# AutomaticSolarTracker.net
KiCad netlist of a schematic drawn in Altium Designer
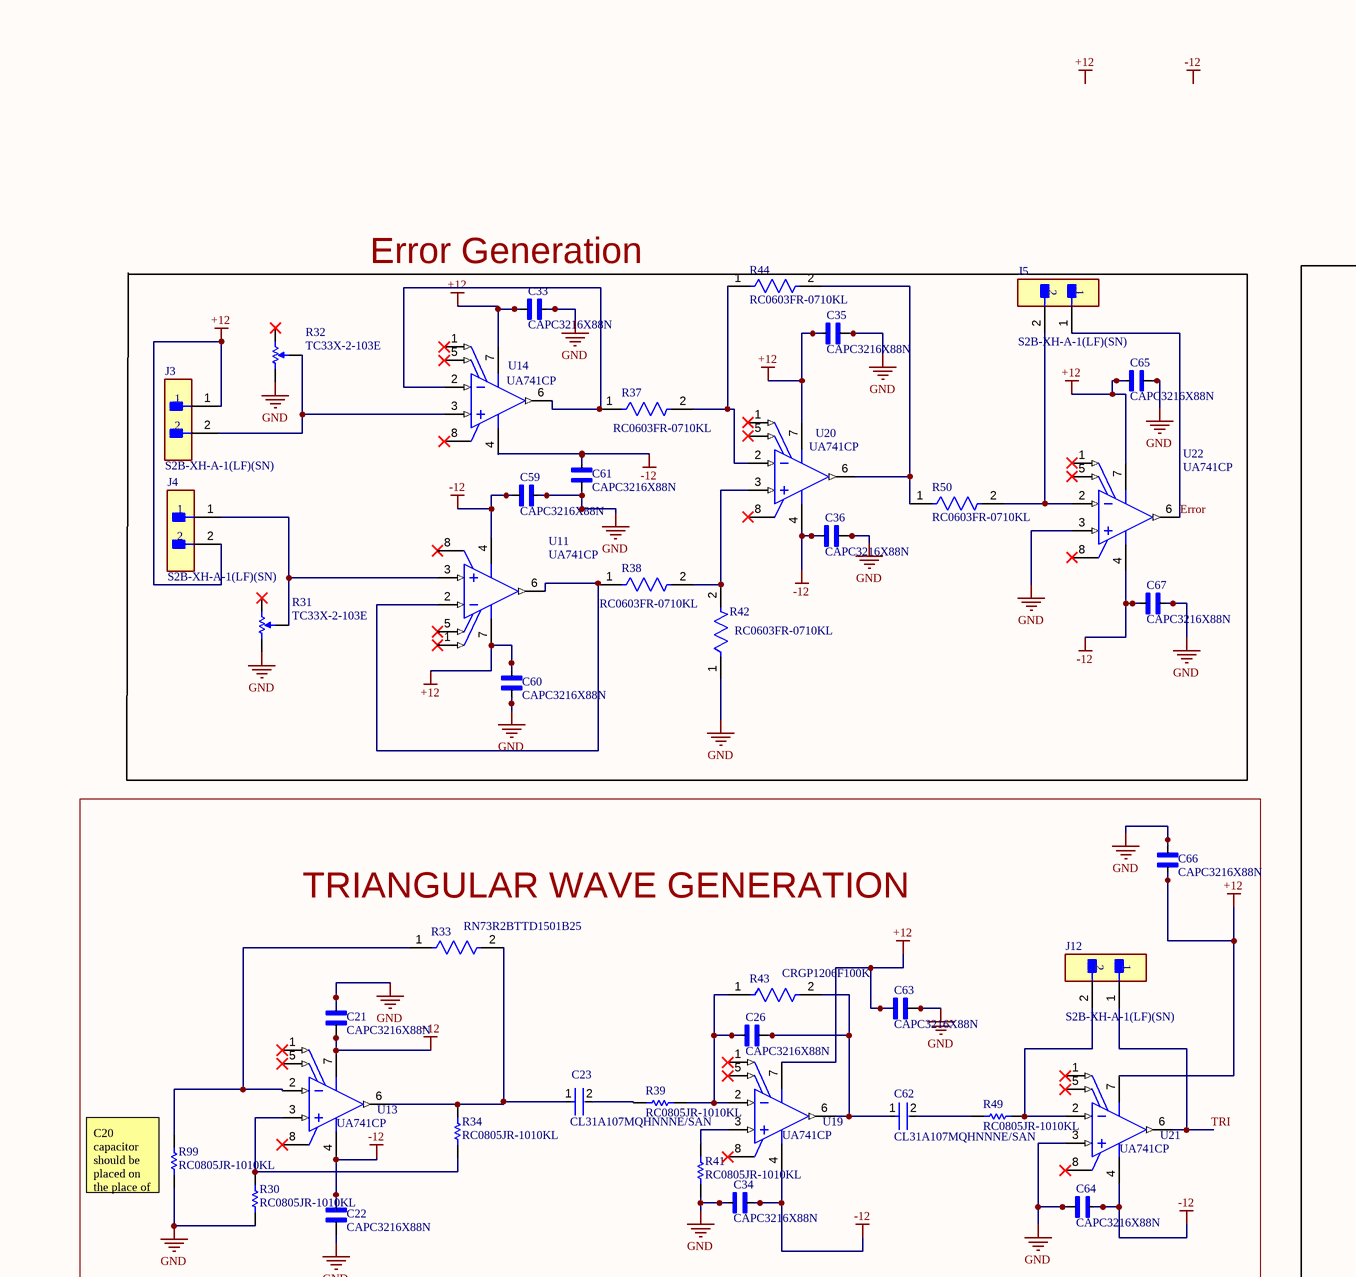
[diagram p0: AutomaticSolarTracker.SchDoc, top left]
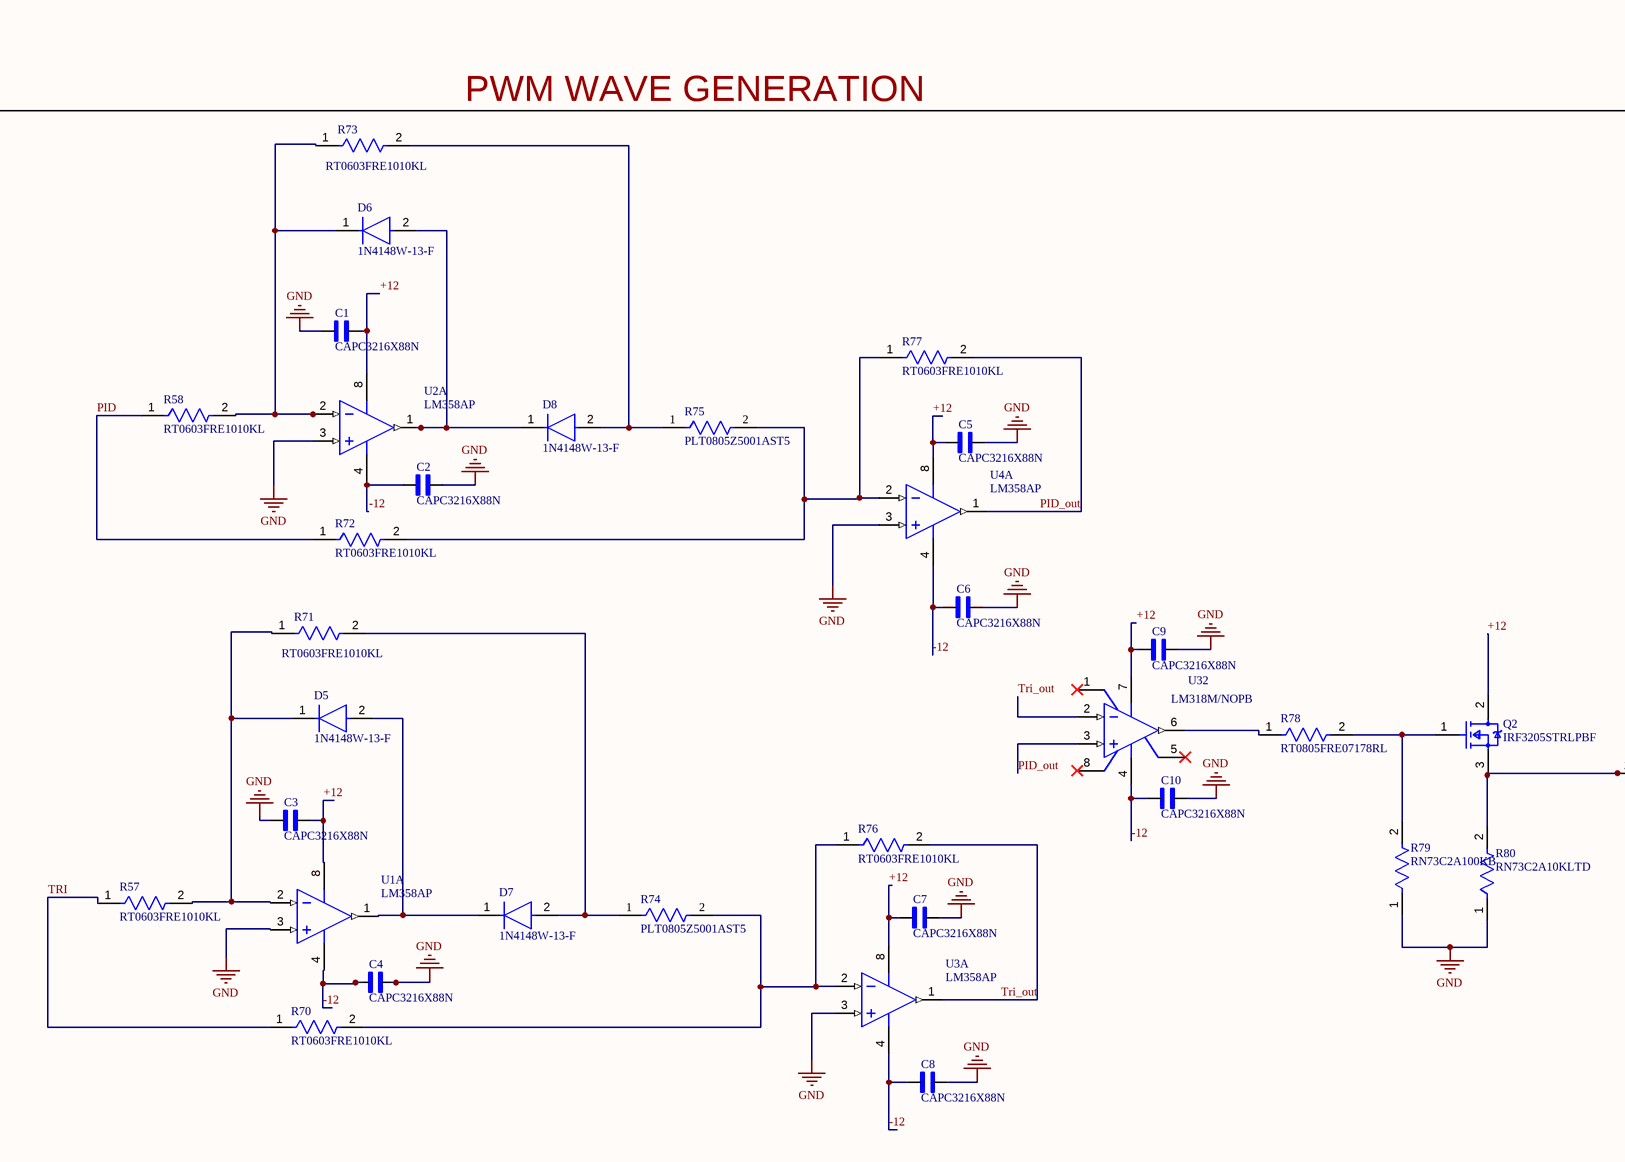
[diagram p1: AutomaticSolarTracker.SchDoc, top middle]
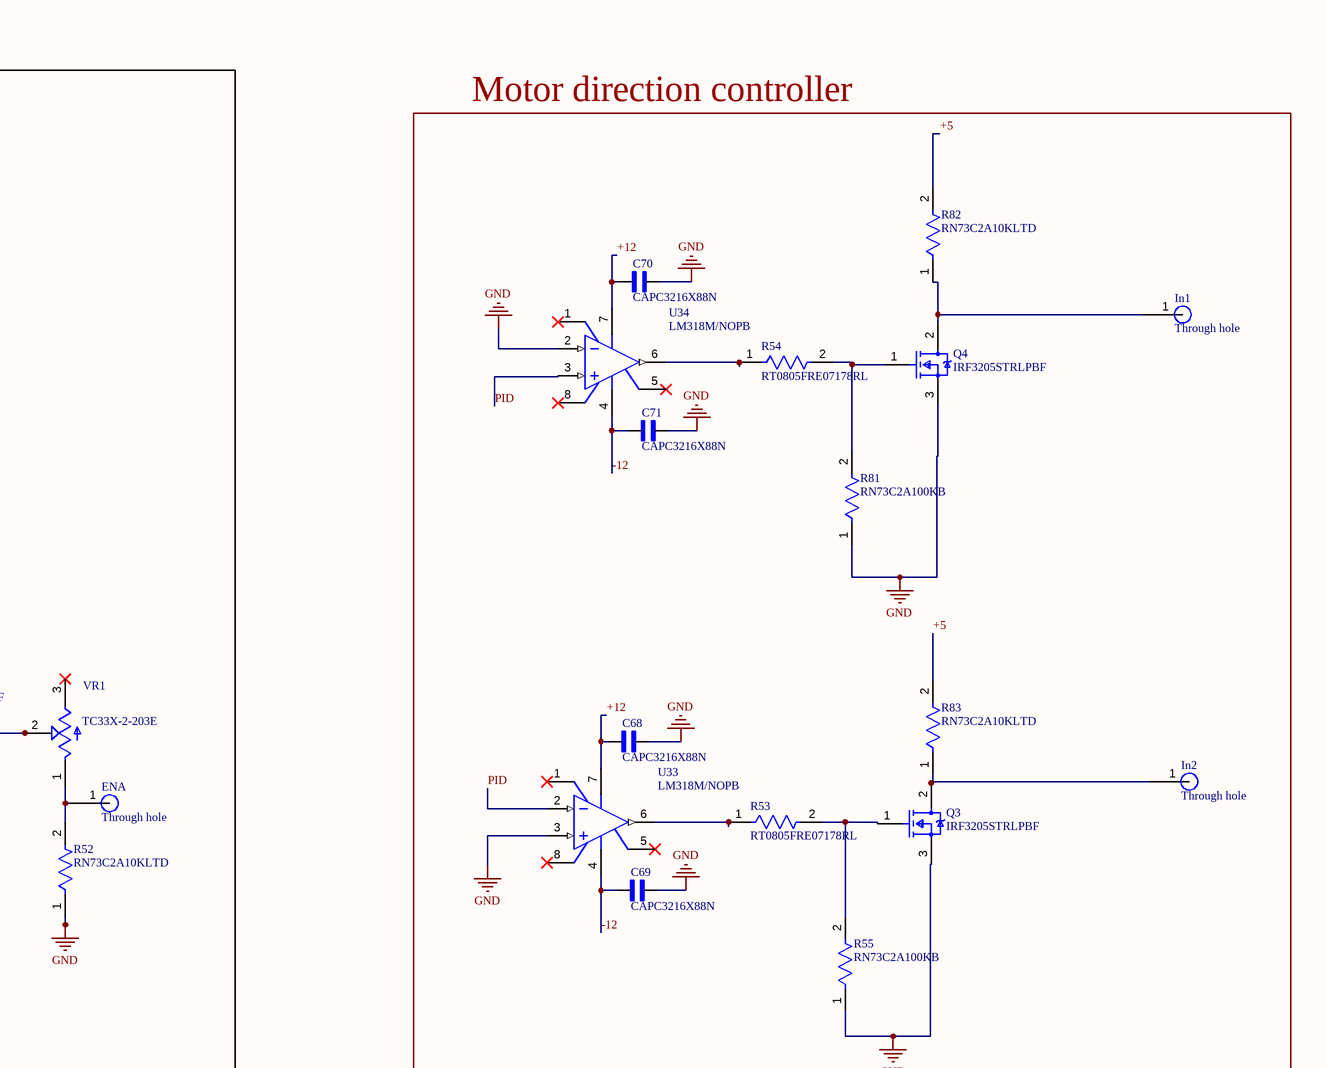
[diagram p2: AutomaticSolarTracker.SchDoc, top right]
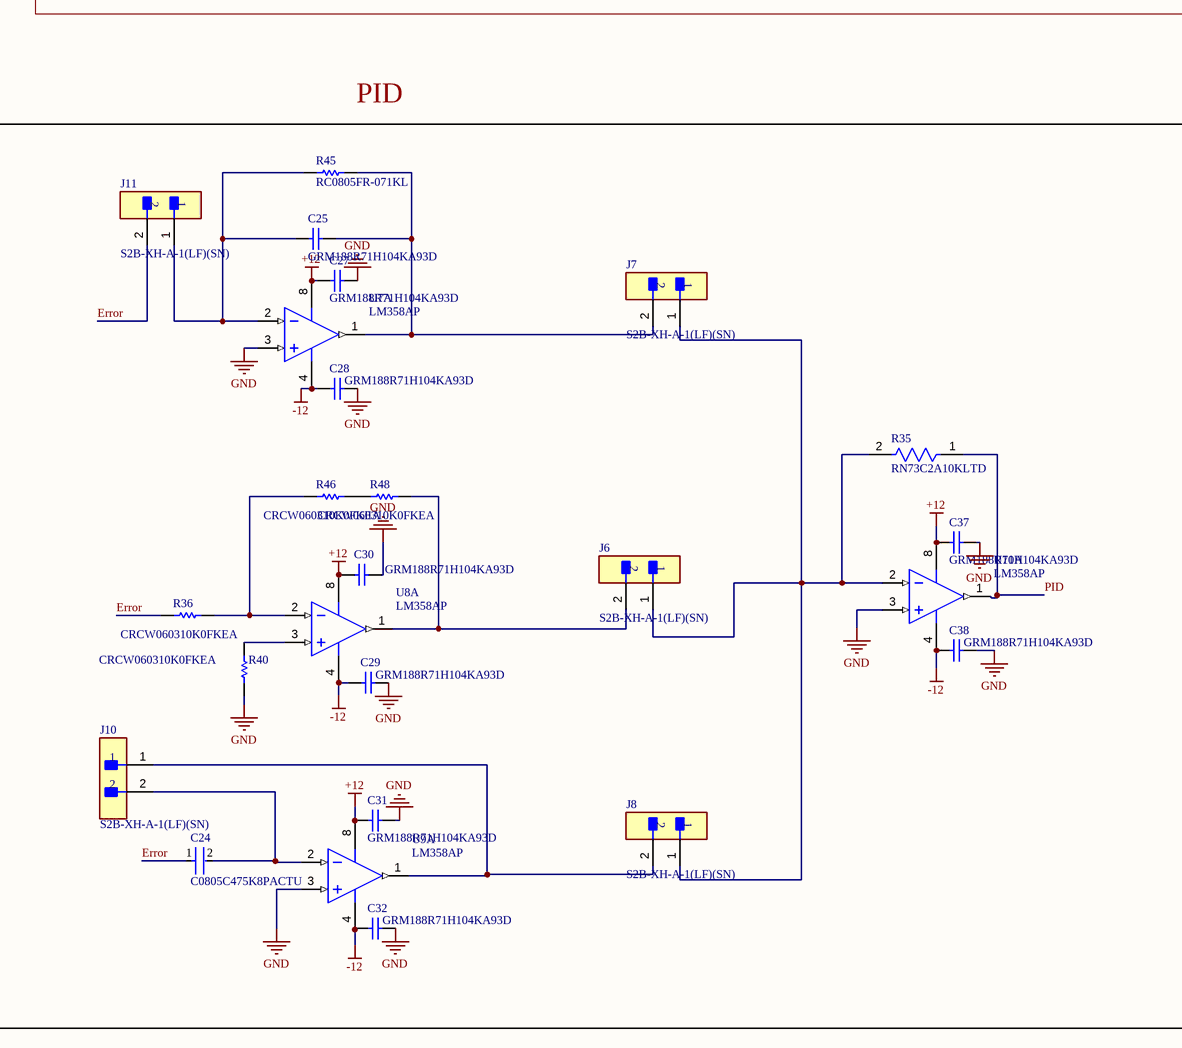
[diagram p3: AutomaticSolarTracker.SchDoc, bottom left]
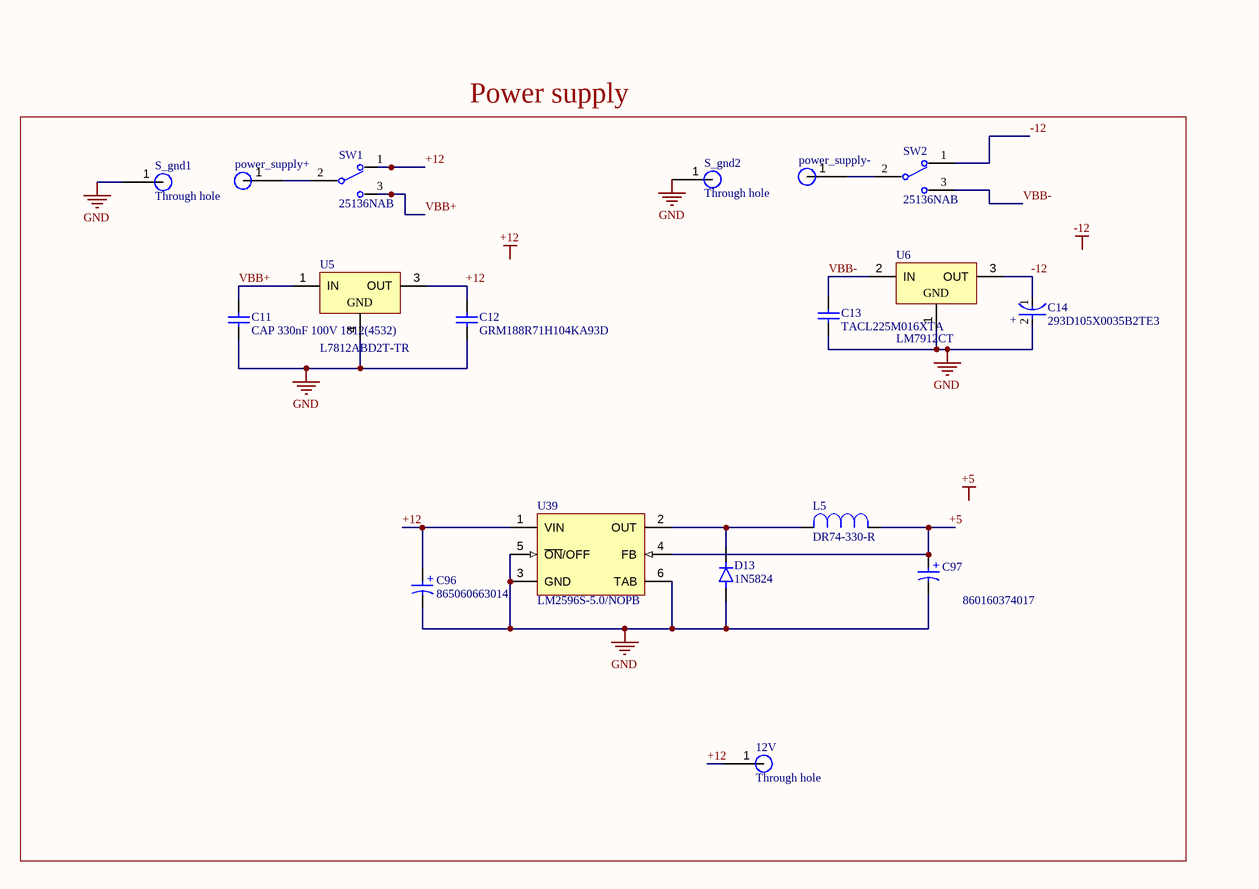
[diagram p4: AutomaticSolarTracker.SchDoc, bottom middle]

(export (version "E")
  (design (tool "Eeschema 10.0.6"))
  (components
    (comp (ref "12V")
      (value "Through hole")
      (footprint "Through hole")
      (libsource (lib "Schlib") (part "Through hole"))
    )
    (comp (ref "C1")
      (value "CAPC3216X88N")
      (footprint "CAPC3216X88N.")
      (description "Multilayer Ceramic Capacitors MLCC - SMD/SMT 50V 0.1uF X7R 1206 10% AEC-Q200")
      (fields
        (field (name "MANUFACTURER") "KEMET")
        (field (name "MANUFACTURER PART NUMBER") "C1206C104K5RACAUTO")
      )
      (libsource (lib "Schlib") (part "CAPC3216X88N"))
    )
    (comp (ref "C2")
      (value "CAPC3216X88N")
      (footprint "CAPC3216X88N.")
      (description "Multilayer Ceramic Capacitors MLCC - SMD/SMT 50V 0.1uF X7R 1206 10% AEC-Q200")
      (fields
        (field (name "MANUFACTURER") "KEMET")
        (field (name "MANUFACTURER PART NUMBER") "C1206C104K5RACAUTO")
      )
      (libsource (lib "Schlib") (part "CAPC3216X88N"))
    )
    (comp (ref "C3")
      (value "CAPC3216X88N")
      (footprint "CAPC3216X88N.")
      (description "Multilayer Ceramic Capacitors MLCC - SMD/SMT 50V 0.1uF X7R 1206 10% AEC-Q200")
      (fields
        (field (name "MANUFACTURER") "KEMET")
        (field (name "MANUFACTURER PART NUMBER") "C1206C104K5RACAUTO")
      )
      (libsource (lib "Schlib") (part "CAPC3216X88N"))
    )
    (comp (ref "C4")
      (value "CAPC3216X88N")
      (footprint "CAPC3216X88N.")
      (description "Multilayer Ceramic Capacitors MLCC - SMD/SMT 50V 0.1uF X7R 1206 10% AEC-Q200")
      (fields
        (field (name "MANUFACTURER") "KEMET")
        (field (name "MANUFACTURER PART NUMBER") "C1206C104K5RACAUTO")
      )
      (libsource (lib "Schlib") (part "CAPC3216X88N"))
    )
    (comp (ref "C5")
      (value "CAPC3216X88N")
      (footprint "CAPC3216X88N.")
      (description "Multilayer Ceramic Capacitors MLCC - SMD/SMT 50V 0.1uF X7R 1206 10% AEC-Q200")
      (fields
        (field (name "MANUFACTURER") "KEMET")
        (field (name "MANUFACTURER PART NUMBER") "C1206C104K5RACAUTO")
      )
      (libsource (lib "Schlib") (part "CAPC3216X88N"))
    )
    (comp (ref "C6")
      (value "CAPC3216X88N")
      (footprint "CAPC3216X88N.")
      (description "Multilayer Ceramic Capacitors MLCC - SMD/SMT 50V 0.1uF X7R 1206 10% AEC-Q200")
      (fields
        (field (name "MANUFACTURER") "KEMET")
        (field (name "MANUFACTURER PART NUMBER") "C1206C104K5RACAUTO")
      )
      (libsource (lib "Schlib") (part "CAPC3216X88N"))
    )
    (comp (ref "C7")
      (value "CAPC3216X88N")
      (footprint "CAPC3216X88N.")
      (description "Multilayer Ceramic Capacitors MLCC - SMD/SMT 50V 0.1uF X7R 1206 10% AEC-Q200")
      (fields
        (field (name "MANUFACTURER") "KEMET")
        (field (name "MANUFACTURER PART NUMBER") "C1206C104K5RACAUTO")
      )
      (libsource (lib "Schlib") (part "CAPC3216X88N"))
    )
    (comp (ref "C8")
      (value "CAPC3216X88N")
      (footprint "CAPC3216X88N.")
      (description "Multilayer Ceramic Capacitors MLCC - SMD/SMT 50V 0.1uF X7R 1206 10% AEC-Q200")
      (fields
        (field (name "MANUFACTURER") "KEMET")
        (field (name "MANUFACTURER PART NUMBER") "C1206C104K5RACAUTO")
      )
      (libsource (lib "Schlib") (part "CAPC3216X88N"))
    )
    (comp (ref "C9")
      (value "CAPC3216X88N")
      (footprint "CAPC3216X88N.")
      (description "Multilayer Ceramic Capacitors MLCC - SMD/SMT 50V 0.1uF X7R 1206 10% AEC-Q200")
      (fields
        (field (name "MANUFACTURER") "KEMET")
        (field (name "MANUFACTURER PART NUMBER") "C1206C104K5RACAUTO")
      )
      (libsource (lib "Schlib") (part "CAPC3216X88N"))
    )
    (comp (ref "C10")
      (value "CAPC3216X88N")
      (footprint "CAPC3216X88N.")
      (description "Multilayer Ceramic Capacitors MLCC - SMD/SMT 50V 0.1uF X7R 1206 10% AEC-Q200")
      (fields
        (field (name "MANUFACTURER") "KEMET")
        (field (name "MANUFACTURER PART NUMBER") "C1206C104K5RACAUTO")
      )
      (libsource (lib "Schlib") (part "CAPC3216X88N"))
    )
    (comp (ref "C11")
      (value "CAP 330nF 100V 1812(4532)")
      (footprint "CAPC1812(4532)125_L")
      (description "CAP 330nF 100V ±20% 1812 (4532 Metric) Thickness 1.25mm SMD")
      (fields (field (name "TOLERANCE") "Â±20%"))
      (libsource (lib "Altium Content Vault") (part "CAP"))
    )
    (comp (ref "C12")
      (value "GRM188R71H104KA93D")
      (footprint "CAPC1608X90X35ML10T15")
      (description "Chip Capacitor, 0.1 uF, +/- 10%, 50 V, -55 to 125 degC, 0603 (1608 Metric), RoHS, Tape and Reel")
      (fields (field (name "TOLERANCE") "10%") (field (name "VOLTAGE") "50V"))
      (libsource (lib "Altium Content Vault") (part "CAP-NP-2"))
    )
    (comp (ref "C13")
      (value "TACL225M016XTA")
      (footprint "CAPC1609X100X15ML20")
      (fields (field (name "MANUFACTURER") "AVX Interconnect / Elco"))
      (libsource (lib "Altium Content Vault") (part "CAP"))
    )
    (comp (ref "C14")
      (value "293D105X0035B2TE3")
      (footprint "FP-293DB-MFG")
      (fields (field (name "TOLERANCE") "20%"))
      (libsource (lib "Altium Content Vault") (part "a00bbbee19879c290e62620ae7e47b1"))
    )
    (comp (ref "C21")
      (value "CAPC3216X88N")
      (footprint "CAPC3216X88N.")
      (description "Multilayer Ceramic Capacitors MLCC - SMD/SMT 50V 0.1uF X7R 1206 10% AEC-Q200")
      (fields
        (field (name "MANUFACTURER") "KEMET")
        (field (name "MANUFACTURER PART NUMBER") "C1206C104K5RACAUTO")
      )
      (libsource (lib "") (part "CAPC3216X88N_1"))
    )
    (comp (ref "C22")
      (value "CAPC3216X88N")
      (footprint "CAPC3216X88N.")
      (description "Multilayer Ceramic Capacitors MLCC - SMD/SMT 50V 0.1uF X7R 1206 10% AEC-Q200")
      (fields
        (field (name "MANUFACTURER") "KEMET")
        (field (name "MANUFACTURER PART NUMBER") "C1206C104K5RACAUTO")
      )
      (libsource (lib "") (part "CAPC3216X88N_1"))
    )
    (comp (ref "C23")
      (value "CL31A107MQHNNNE/SAN")
      (footprint "FP-CL31-IPC_C")
      (description "Cap Ceramic 100uF 6.3V X5R ±20% SMD 1206 +85°C Embossed T/R")
      (libsource (lib "Altium Content Vault") (part "b4654b650e69147ec39a6b967a45e02"))
    )
    (comp (ref "C24")
      (value "C0805C475K8PACTU")
      (footprint "FP-C0805C475K8PACTU-MFG")
      (description "CAP CER 4.7UF 10V X5R 0805")
      (fields (field (name "TOLERANCE") "10%") (field (name "VOLTAGE") "10V"))
      (libsource (lib "Altium Content Vault") (part "e9c51b7dd13d4faca003ae77663ab08"))
    )
    (comp (ref "C25")
      (value "GRM188R71H104KA93D")
      (footprint "CAPC1608X90X35ML10T15")
      (description "Chip Capacitor, 0.1 uF, +/- 10%, 50 V, -55 to 125 degC, 0603 (1608 Metric), RoHS, Tape and Reel")
      (fields (field (name "TOLERANCE") "10%") (field (name "VOLTAGE") "50V"))
      (libsource (lib "Altium Content Vault") (part "CAP-NP-2"))
    )
    (comp (ref "C26")
      (value "CAPC3216X88N")
      (footprint "CAPC3216X88N.")
      (description "Multilayer Ceramic Capacitors MLCC - SMD/SMT 50V 0.1uF X7R 1206 10% AEC-Q200")
      (fields
        (field (name "MANUFACTURER") "KEMET")
        (field (name "MANUFACTURER PART NUMBER") "C1206C104K5RACAUTO")
      )
      (libsource (lib "Schlib") (part "CAPC3216X88N"))
    )
    (comp (ref "C27")
      (value "GRM188R71H104KA93D")
      (footprint "CAPC1608X90X35ML10T15")
      (description "Chip Capacitor, 0.1 uF, +/- 10%, 50 V, -55 to 125 degC, 0603 (1608 Metric), RoHS, Tape and Reel")
      (fields (field (name "TOLERANCE") "10%") (field (name "VOLTAGE") "50V"))
      (libsource (lib "Altium Content Vault") (part "CAP-NP-2"))
    )
    (comp (ref "C28")
      (value "GRM188R71H104KA93D")
      (footprint "CAPC1608X90X35ML10T15")
      (description "Chip Capacitor, 0.1 uF, +/- 10%, 50 V, -55 to 125 degC, 0603 (1608 Metric), RoHS, Tape and Reel")
      (fields (field (name "TOLERANCE") "10%") (field (name "VOLTAGE") "50V"))
      (libsource (lib "Altium Content Vault") (part "CAP-NP-2"))
    )
    (comp (ref "C29")
      (value "GRM188R71H104KA93D")
      (footprint "CAPC1608X90X35ML10T15")
      (description "Chip Capacitor, 0.1 uF, +/- 10%, 50 V, -55 to 125 degC, 0603 (1608 Metric), RoHS, Tape and Reel")
      (fields (field (name "TOLERANCE") "10%") (field (name "VOLTAGE") "50V"))
      (libsource (lib "Altium Content Vault") (part "CAP-NP-2"))
    )
    (comp (ref "C30")
      (value "GRM188R71H104KA93D")
      (footprint "CAPC1608X90X35ML10T15")
      (description "Chip Capacitor, 0.1 uF, +/- 10%, 50 V, -55 to 125 degC, 0603 (1608 Metric), RoHS, Tape and Reel")
      (fields (field (name "TOLERANCE") "10%") (field (name "VOLTAGE") "50V"))
      (libsource (lib "Altium Content Vault") (part "CAP-NP-2"))
    )
    (comp (ref "C31")
      (value "GRM188R71H104KA93D")
      (footprint "CAPC1608X90X35ML10T15")
      (description "Chip Capacitor, 0.1 uF, +/- 10%, 50 V, -55 to 125 degC, 0603 (1608 Metric), RoHS, Tape and Reel")
      (fields (field (name "TOLERANCE") "10%") (field (name "VOLTAGE") "50V"))
      (libsource (lib "Altium Content Vault") (part "CAP-NP-2"))
    )
    (comp (ref "C32")
      (value "GRM188R71H104KA93D")
      (footprint "CAPC1608X90X35ML10T15")
      (description "Chip Capacitor, 0.1 uF, +/- 10%, 50 V, -55 to 125 degC, 0603 (1608 Metric), RoHS, Tape and Reel")
      (fields (field (name "TOLERANCE") "10%") (field (name "VOLTAGE") "50V"))
      (libsource (lib "Altium Content Vault") (part "CAP-NP-2"))
    )
    (comp (ref "C33")
      (value "CAPC3216X88N")
      (footprint "CAPC3216X88N.")
      (description "Multilayer Ceramic Capacitors MLCC - SMD/SMT 50V 0.1uF X7R 1206 10% AEC-Q200")
      (fields
        (field (name "MANUFACTURER") "KEMET")
        (field (name "MANUFACTURER PART NUMBER") "C1206C104K5RACAUTO")
      )
      (libsource (lib "Schlib") (part "CAPC3216X88N"))
    )
    (comp (ref "C34")
      (value "CAPC3216X88N")
      (footprint "CAPC3216X88N.")
      (description "Multilayer Ceramic Capacitors MLCC - SMD/SMT 50V 0.1uF X7R 1206 10% AEC-Q200")
      (fields
        (field (name "MANUFACTURER") "KEMET")
        (field (name "MANUFACTURER PART NUMBER") "C1206C104K5RACAUTO")
      )
      (libsource (lib "Schlib") (part "CAPC3216X88N"))
    )
    (comp (ref "C35")
      (value "CAPC3216X88N")
      (footprint "CAPC3216X88N.")
      (description "Multilayer Ceramic Capacitors MLCC - SMD/SMT 50V 0.1uF X7R 1206 10% AEC-Q200")
      (fields
        (field (name "MANUFACTURER") "KEMET")
        (field (name "MANUFACTURER PART NUMBER") "C1206C104K5RACAUTO")
      )
      (libsource (lib "Schlib") (part "CAPC3216X88N"))
    )
    (comp (ref "C36")
      (value "CAPC3216X88N")
      (footprint "CAPC3216X88N.")
      (description "Multilayer Ceramic Capacitors MLCC - SMD/SMT 50V 0.1uF X7R 1206 10% AEC-Q200")
      (fields
        (field (name "MANUFACTURER") "KEMET")
        (field (name "MANUFACTURER PART NUMBER") "C1206C104K5RACAUTO")
      )
      (libsource (lib "Schlib") (part "CAPC3216X88N"))
    )
    (comp (ref "C37")
      (value "GRM188R71H104KA93D")
      (footprint "CAPC1608X90X35ML10T15")
      (description "Chip Capacitor, 0.1 uF, +/- 10%, 50 V, -55 to 125 degC, 0603 (1608 Metric), RoHS, Tape and Reel")
      (fields (field (name "TOLERANCE") "10%") (field (name "VOLTAGE") "50V"))
      (libsource (lib "Altium Content Vault") (part "CAP-NP-2"))
    )
    (comp (ref "C38")
      (value "GRM188R71H104KA93D")
      (footprint "CAPC1608X90X35ML10T15")
      (description "Chip Capacitor, 0.1 uF, +/- 10%, 50 V, -55 to 125 degC, 0603 (1608 Metric), RoHS, Tape and Reel")
      (fields (field (name "TOLERANCE") "10%") (field (name "VOLTAGE") "50V"))
      (libsource (lib "Altium Content Vault") (part "CAP-NP-2"))
    )
    (comp (ref "C59")
      (value "CAPC3216X88N")
      (footprint "CAPC3216X88N.")
      (description "Multilayer Ceramic Capacitors MLCC - SMD/SMT 50V 0.1uF X7R 1206 10% AEC-Q200")
      (fields
        (field (name "MANUFACTURER") "KEMET")
        (field (name "MANUFACTURER PART NUMBER") "C1206C104K5RACAUTO")
      )
      (libsource (lib "Schlib") (part "CAPC3216X88N"))
    )
    (comp (ref "C60")
      (value "CAPC3216X88N")
      (footprint "CAPC3216X88N.")
      (description "Multilayer Ceramic Capacitors MLCC - SMD/SMT 50V 0.1uF X7R 1206 10% AEC-Q200")
      (fields
        (field (name "MANUFACTURER") "KEMET")
        (field (name "MANUFACTURER PART NUMBER") "C1206C104K5RACAUTO")
      )
      (libsource (lib "") (part "CAPC3216X88N_1"))
    )
    (comp (ref "C61")
      (value "CAPC3216X88N")
      (footprint "CAPC3216X88N.")
      (description "Multilayer Ceramic Capacitors MLCC - SMD/SMT 50V 0.1uF X7R 1206 10% AEC-Q200")
      (fields
        (field (name "MANUFACTURER") "KEMET")
        (field (name "MANUFACTURER PART NUMBER") "C1206C104K5RACAUTO")
      )
      (libsource (lib "") (part "CAPC3216X88N_1"))
    )
    (comp (ref "C62")
      (value "CL31A107MQHNNNE/SAN")
      (footprint "FP-CL31-IPC_C")
      (description "Cap Ceramic 100uF 6.3V X5R ±20% SMD 1206 +85°C Embossed T/R")
      (libsource (lib "Altium Content Vault") (part "b4654b650e69147ec39a6b967a45e02"))
    )
    (comp (ref "C63")
      (value "CAPC3216X88N")
      (footprint "CAPC3216X88N.")
      (description "Multilayer Ceramic Capacitors MLCC - SMD/SMT 50V 0.1uF X7R 1206 10% AEC-Q200")
      (fields
        (field (name "MANUFACTURER") "KEMET")
        (field (name "MANUFACTURER PART NUMBER") "C1206C104K5RACAUTO")
      )
      (libsource (lib "Schlib") (part "CAPC3216X88N"))
    )
    (comp (ref "C64")
      (value "CAPC3216X88N")
      (footprint "CAPC3216X88N.")
      (description "Multilayer Ceramic Capacitors MLCC - SMD/SMT 50V 0.1uF X7R 1206 10% AEC-Q200")
      (fields
        (field (name "MANUFACTURER") "KEMET")
        (field (name "MANUFACTURER PART NUMBER") "C1206C104K5RACAUTO")
      )
      (libsource (lib "Schlib") (part "CAPC3216X88N"))
    )
    (comp (ref "C65")
      (value "CAPC3216X88N")
      (footprint "CAPC3216X88N.")
      (description "Multilayer Ceramic Capacitors MLCC - SMD/SMT 50V 0.1uF X7R 1206 10% AEC-Q200")
      (fields
        (field (name "MANUFACTURER") "KEMET")
        (field (name "MANUFACTURER PART NUMBER") "C1206C104K5RACAUTO")
      )
      (libsource (lib "Schlib") (part "CAPC3216X88N"))
    )
    (comp (ref "C66")
      (value "CAPC3216X88N")
      (footprint "CAPC3216X88N.")
      (description "Multilayer Ceramic Capacitors MLCC - SMD/SMT 50V 0.1uF X7R 1206 10% AEC-Q200")
      (fields
        (field (name "MANUFACTURER") "KEMET")
        (field (name "MANUFACTURER PART NUMBER") "C1206C104K5RACAUTO")
      )
      (libsource (lib "") (part "CAPC3216X88N_1"))
    )
    (comp (ref "C67")
      (value "CAPC3216X88N")
      (footprint "CAPC3216X88N.")
      (description "Multilayer Ceramic Capacitors MLCC - SMD/SMT 50V 0.1uF X7R 1206 10% AEC-Q200")
      (fields
        (field (name "MANUFACTURER") "KEMET")
        (field (name "MANUFACTURER PART NUMBER") "C1206C104K5RACAUTO")
      )
      (libsource (lib "Schlib") (part "CAPC3216X88N"))
    )
    (comp (ref "C68")
      (value "CAPC3216X88N")
      (footprint "CAPC3216X88N.")
      (description "Multilayer Ceramic Capacitors MLCC - SMD/SMT 50V 0.1uF X7R 1206 10% AEC-Q200")
      (fields
        (field (name "MANUFACTURER") "KEMET")
        (field (name "MANUFACTURER PART NUMBER") "C1206C104K5RACAUTO")
      )
      (libsource (lib "Schlib") (part "CAPC3216X88N"))
    )
    (comp (ref "C69")
      (value "CAPC3216X88N")
      (footprint "CAPC3216X88N.")
      (description "Multilayer Ceramic Capacitors MLCC - SMD/SMT 50V 0.1uF X7R 1206 10% AEC-Q200")
      (fields
        (field (name "MANUFACTURER") "KEMET")
        (field (name "MANUFACTURER PART NUMBER") "C1206C104K5RACAUTO")
      )
      (libsource (lib "Schlib") (part "CAPC3216X88N"))
    )
    (comp (ref "C70")
      (value "CAPC3216X88N")
      (footprint "CAPC3216X88N.")
      (description "Multilayer Ceramic Capacitors MLCC - SMD/SMT 50V 0.1uF X7R 1206 10% AEC-Q200")
      (fields
        (field (name "MANUFACTURER") "KEMET")
        (field (name "MANUFACTURER PART NUMBER") "C1206C104K5RACAUTO")
      )
      (libsource (lib "Schlib") (part "CAPC3216X88N"))
    )
    (comp (ref "C71")
      (value "CAPC3216X88N")
      (footprint "CAPC3216X88N.")
      (description "Multilayer Ceramic Capacitors MLCC - SMD/SMT 50V 0.1uF X7R 1206 10% AEC-Q200")
      (fields
        (field (name "MANUFACTURER") "KEMET")
        (field (name "MANUFACTURER PART NUMBER") "C1206C104K5RACAUTO")
      )
      (libsource (lib "Schlib") (part "CAPC3216X88N"))
    )
    (comp (ref "C96")
      (value "865060663014")
      (footprint "WCAP-ASLL_D16H17")
      (description "865060663014 WCAP-ASLL Aluminum Electrolytic Capacitors")
      (fields (field (name "TOLERANCE") "20%"))
      (libsource (lib "Altium Content Vault") (part "Capacitor_Polarized"))
    )
    (comp (ref "C97")
      (value "860160374017")
      (footprint "WCAP-ATLL_D8H11.5")
      (description "860160374017 Aluminium Electrolytic Capacitor-Leaded Rohs Compliant: Yes")
      (libsource (lib "Altium Content Vault") (part "Capacitor_Polarized"))
    )
    (comp (ref "D5")
      (value "1N4148W-13-F")
      (footprint "FP-SOD123-MFG")
      (description "DIODE GEN PURP 100V 150MA SOD123")
      (fields
        (field (name "OCTOPART") "https://octopart.com/1n4148w-13-f-diodes+inc.-2359612")
        (field (name "MANUFACTURER") "Diodes Inc.")
      )
      (libsource (lib "Altium Content Vault") (part "d7152d700b627762746794eb795d46e"))
    )
    (comp (ref "D6")
      (value "1N4148W-13-F")
      (footprint "FP-SOD123-MFG")
      (description "DIODE GEN PURP 100V 150MA SOD123")
      (fields
        (field (name "OCTOPART") "https://octopart.com/1n4148w-13-f-diodes+inc.-2359612")
        (field (name "MANUFACTURER") "Diodes Inc.")
      )
      (libsource (lib "Altium Content Vault") (part "d7152d700b627762746794eb795d46e"))
    )
    (comp (ref "D7")
      (value "1N4148W-13-F")
      (footprint "FP-SOD123-MFG")
      (description "DIODE GEN PURP 100V 150MA SOD123")
      (fields
        (field (name "OCTOPART") "https://octopart.com/1n4148w-13-f-diodes+inc.-2359612")
        (field (name "MANUFACTURER") "Diodes Inc.")
      )
      (libsource (lib "Altium Content Vault") (part "d7152d700b627762746794eb795d46e"))
    )
    (comp (ref "D8")
      (value "1N4148W-13-F")
      (footprint "FP-SOD123-MFG")
      (description "DIODE GEN PURP 100V 150MA SOD123")
      (fields
        (field (name "OCTOPART") "https://octopart.com/1n4148w-13-f-diodes+inc.-2359612")
        (field (name "MANUFACTURER") "Diodes Inc.")
      )
      (libsource (lib "Altium Content Vault") (part "d7152d700b627762746794eb795d46e"))
    )
    (comp (ref "D13")
      (value "1N5824")
      (footprint "DIOAD")
      (description "Rectifier Diode, Schottky, 1 Phase, 1 Element, 5A, 30V V(RRM), Silicon")
      (fields (field (name "MANUFACTURER") "Microchip"))
      (libsource (lib "Schlib") (part "1N5824"))
    )
    (comp (ref "ENA")
      (value "Through hole")
      (footprint "Through hole")
      (libsource (lib "Schlib") (part "Through hole"))
    )
    (comp (ref "In1")
      (value "Through hole")
      (footprint "Through hole")
      (libsource (lib "Schlib") (part "Through hole"))
    )
    (comp (ref "In2")
      (value "Through hole")
      (footprint "Through hole")
      (libsource (lib "Schlib") (part "Through hole"))
    )
    (comp (ref "J3")
      (value "S2B-XH-A-1(LF)(SN)")
      (footprint "FP-S2B-XH-A-1_LF_SN-MFG")
      (description "CONN HEADER R/A 2POS 2.5MM")
      (libsource (lib "Altium Content Vault") (part "3bc925449376181038e59eaffc5286c"))
    )
    (comp (ref "J4")
      (value "S2B-XH-A-1(LF)(SN)")
      (footprint "FP-S2B-XH-A-1_LF_SN-MFG")
      (description "CONN HEADER R/A 2POS 2.5MM")
      (libsource (lib "Altium Content Vault") (part "3bc925449376181038e59eaffc5286c"))
    )
    (comp (ref "J5")
      (value "S2B-XH-A-1(LF)(SN)")
      (footprint "FP-S2B-XH-A-1_LF_SN-MFG")
      (description "CONN HEADER R/A 2POS 2.5MM")
      (libsource (lib "") (part "3bc925449376181038e59eaffc5286c_1"))
    )
    (comp (ref "J6")
      (value "S2B-XH-A-1(LF)(SN)")
      (footprint "FP-S2B-XH-A-1_LF_SN-MFG")
      (description "CONN HEADER R/A 2POS 2.5MM")
      (libsource (lib "") (part "3bc925449376181038e59eaffc5286c_1"))
    )
    (comp (ref "J7")
      (value "S2B-XH-A-1(LF)(SN)")
      (footprint "FP-S2B-XH-A-1_LF_SN-MFG")
      (description "CONN HEADER R/A 2POS 2.5MM")
      (libsource (lib "") (part "3bc925449376181038e59eaffc5286c_1"))
    )
    (comp (ref "J8")
      (value "S2B-XH-A-1(LF)(SN)")
      (footprint "FP-S2B-XH-A-1_LF_SN-MFG")
      (description "CONN HEADER R/A 2POS 2.5MM")
      (libsource (lib "") (part "3bc925449376181038e59eaffc5286c_1"))
    )
    (comp (ref "J10")
      (value "S2B-XH-A-1(LF)(SN)")
      (footprint "FP-S2B-XH-A-1_LF_SN-MFG")
      (description "CONN HEADER R/A 2POS 2.5MM")
      (libsource (lib "Altium Content Vault") (part "3bc925449376181038e59eaffc5286c"))
    )
    (comp (ref "J11")
      (value "S2B-XH-A-1(LF)(SN)")
      (footprint "FP-S2B-XH-A-1_LF_SN-MFG")
      (description "CONN HEADER R/A 2POS 2.5MM")
      (libsource (lib "") (part "3bc925449376181038e59eaffc5286c_1"))
    )
    (comp (ref "J12")
      (value "S2B-XH-A-1(LF)(SN)")
      (footprint "FP-S2B-XH-A-1_LF_SN-MFG")
      (description "CONN HEADER R/A 2POS 2.5MM")
      (libsource (lib "") (part "3bc925449376181038e59eaffc5286c_1"))
    )
    (comp (ref "L5")
      (value "DR74-330-R")
      (footprint "DR74-330-R")
      (description "Inductor Power Shielded Drum Core 33uH 20% 100KHz Ferrite 1.41A 143mOhm DCR T/R")
      (fields (field (name "MANUFACTURER") "Eaton") (field (name "TOLERANCE") "20%"))
      (libsource (lib "Schlib") (part "DR74-330-R"))
    )
    (comp (ref "power_supply+")
      (value "~")
      (footprint "Through hole")
      (libsource (lib "Schlib") (part "Through hole"))
    )
    (comp (ref "power_supply-")
      (value "~")
      (footprint "Through hole")
      (libsource (lib "Schlib") (part "Through hole"))
    )
    (comp (ref "Q2")
      (value "IRF3205STRLPBF")
      (footprint "FP-PG-TO263-3-MFG")
      (description "MOSFET N-CH 55V 110A D2PAK")
      (fields
        (field (name "MANUFACTURER") "Infineon Technologies")
        (field (name "OCTOPART") "https://octopart.com/irf3205strlpbf-infineon-65873335")
      )
      (libsource (lib "Altium Content Vault") (part "b09f7f152735e370c1ea22a33fa83d6"))
    )
    (comp (ref "Q3")
      (value "IRF3205STRLPBF")
      (footprint "FP-PG-TO263-3-MFG")
      (description "MOSFET N-CH 55V 110A D2PAK")
      (fields
        (field (name "MANUFACTURER") "Infineon Technologies")
        (field (name "OCTOPART") "https://octopart.com/irf3205strlpbf-infineon-65873335")
      )
      (libsource (lib "Altium Content Vault") (part "b09f7f152735e370c1ea22a33fa83d6"))
    )
    (comp (ref "Q4")
      (value "IRF3205STRLPBF")
      (footprint "FP-PG-TO263-3-MFG")
      (description "MOSFET N-CH 55V 110A D2PAK")
      (fields
        (field (name "MANUFACTURER") "Infineon Technologies")
        (field (name "OCTOPART") "https://octopart.com/irf3205strlpbf-infineon-65873335")
      )
      (libsource (lib "Altium Content Vault") (part "b09f7f152735e370c1ea22a33fa83d6"))
    )
    (comp (ref "R30")
      (value "RC0805JR-1010KL")
      (footprint "RESC2013X60X35NL10T20")
      (fields (field (name "MANUFACTURER") "Yageo"))
      (libsource (lib "Altium Content Vault") (part "RES"))
    )
    (comp (ref "R31")
      (value "TC33X-2-103E")
      (footprint "BOUR-TC33X-2_V")
      (description "Trimming Potentiometer, 10000 Ohm, -40 to 100 degC, 3-Pin SMD, RoHS, Tape and Reel")
      (fields (field (name "TOLERANCE") "25%") (field (name "MANUFACTURER") "Bourns"))
      (libsource (lib "Altium Content Vault") (part "RES-ADJ-3_A"))
    )
    (comp (ref "R32")
      (value "TC33X-2-103E")
      (footprint "BOUR-TC33X-2_V")
      (description "Trimming Potentiometer, 10000 Ohm, -40 to 100 degC, 3-Pin SMD, RoHS, Tape and Reel")
      (fields (field (name "TOLERANCE") "25%") (field (name "MANUFACTURER") "Bourns"))
      (libsource (lib "Altium Content Vault") (part "RES-ADJ-3_A"))
    )
    (comp (ref "R33")
      (value "RN73R2BTTD1501B25")
      (footprint "FP-RN73R2B-IPC_A")
      (description "1.5kΩ ±0.1% 0.25W, 1/4W Chip Resistor 1206 (3216 Metric) Moisture Resistant Thin Film")
      (libsource (lib "Altium Content Vault") (part "1029c3af85768c4190bb7ad29bc67b5"))
    )
    (comp (ref "R34")
      (value "RC0805JR-1010KL")
      (footprint "RESC2013X60X35NL10T20")
      (fields (field (name "MANUFACTURER") "Yageo"))
      (libsource (lib "Altium Content Vault") (part "RES"))
    )
    (comp (ref "R35")
      (value "RN73C2A10KLTD")
      (footprint "FP-RN732A-MFG")
      (description "SMD Chip Resistor, Thin Film, 10.LKΩ, 100 V, 0805 [2012 Metric], 100 mW, 0.1%, RN73 Series")
      (fields
        (field (name "TOLERANCE") "42")
        (field (name "OCTOPART") "https://octopart.com/rn73c2a10kltd-te+connectivity-22738660")
      )
      (libsource (lib "Altium Content Vault") (part "1029c3af85768c4190bb7ad29bc67b5"))
    )
    (comp (ref "R36")
      (value "CRCW060310K0FKEA")
      (footprint "RESC1609X50X30NL8T20")
      (description "Chip Resistor, 10 KOhm, +/- 1%, 100 mW, -55 to 155 degC, 0603 (1608 Metric), RoHS, Tape and Reel")
      (fields (field (name "MANUFACTURER") "Vishay Semiconductor"))
      (libsource (lib "Altium Content Vault") (part "RES-2"))
    )
    (comp (ref "R37")
      (value "RC0603FR-0710KL")
      (footprint "FP-RC0603-0_55-IPC_C")
      (description "RES 10K OHM 1% 1/10W 0603")
      (fields (field (name "TOLERANCE") "1%"))
      (libsource (lib "Altium Content Vault") (part "1029c3af85768c4190bb7ad29bc67b5"))
    )
    (comp (ref "R38")
      (value "RC0603FR-0710KL")
      (footprint "FP-RC0603-0_55-IPC_C")
      (description "RES 10K OHM 1% 1/10W 0603")
      (fields (field (name "TOLERANCE") "1%"))
      (libsource (lib "Altium Content Vault") (part "1029c3af85768c4190bb7ad29bc67b5"))
    )
    (comp (ref "R39")
      (value "RC0805JR-1010KL")
      (footprint "RESC2013X60X35NL10T20")
      (fields (field (name "MANUFACTURER") "Yageo"))
      (libsource (lib "Altium Content Vault") (part "RES"))
    )
    (comp (ref "R40")
      (value "CRCW060310K0FKEA")
      (footprint "RESC1609X50X30NL8T20")
      (description "Chip Resistor, 10 KOhm, +/- 1%, 100 mW, -55 to 155 degC, 0603 (1608 Metric), RoHS, Tape and Reel")
      (fields (field (name "MANUFACTURER") "Vishay Semiconductor"))
      (libsource (lib "Altium Content Vault") (part "RES-2"))
    )
    (comp (ref "R41")
      (value "RC0805JR-1010KL")
      (footprint "RESC2013X60X35NL10T20")
      (fields (field (name "MANUFACTURER") "Yageo"))
      (libsource (lib "Altium Content Vault") (part "RES"))
    )
    (comp (ref "R42")
      (value "RC0603FR-0710KL")
      (footprint "FP-RC0603-0_55-IPC_C")
      (description "RES 10K OHM 1% 1/10W 0603")
      (fields (field (name "TOLERANCE") "1%"))
      (libsource (lib "Altium Content Vault") (part "1029c3af85768c4190bb7ad29bc67b5"))
    )
    (comp (ref "R43")
      (value "CRGP1206F100K")
      (footprint "FP-CRGP1206-IPC_C")
      (description "CRGP1206 100KΩ 0.5W ±100ppm/°C 1% 200V")
      (fields (field (name "MANUFACTURER") "TE") (field (name "TOLERANCE") "0.01"))
      (libsource (lib "Altium Content Vault") (part "1029c3af85768c4190bb7ad29bc67b5"))
    )
    (comp (ref "R44")
      (value "RC0603FR-0710KL")
      (footprint "FP-RC0603-0_55-IPC_C")
      (description "RES 10K OHM 1% 1/10W 0603")
      (fields (field (name "TOLERANCE") "1%"))
      (libsource (lib "Altium Content Vault") (part "1029c3af85768c4190bb7ad29bc67b5"))
    )
    (comp (ref "R45")
      (value "RC0805FR-071KL")
      (footprint "RESC2013X60X35ML10T20")
      (description "Chip Resistor, 1 KOhm, +/- 1%, 125 mW, -55 to 155 degC, 0805 (2012 Metric), RoHS, Tape and Reel")
      (fields (field (name "TOLERANCE") "1%") (field (name "MANUFACTURER") "Yageo"))
      (libsource (lib "Altium Content Vault") (part "RES-2"))
    )
    (comp (ref "R46")
      (value "CRCW060310K0FKEA")
      (footprint "RESC1609X50X30NL8T20")
      (description "Chip Resistor, 10 KOhm, +/- 1%, 100 mW, -55 to 155 degC, 0603 (1608 Metric), RoHS, Tape and Reel")
      (fields (field (name "MANUFACTURER") "Vishay Semiconductor"))
      (libsource (lib "Altium Content Vault") (part "RES-2"))
    )
    (comp (ref "R48")
      (value "CRCW060310K0FKEA")
      (footprint "RESC1609X50X30NL8T20")
      (description "Chip Resistor, 10 KOhm, +/- 1%, 100 mW, -55 to 155 degC, 0603 (1608 Metric), RoHS, Tape and Reel")
      (fields (field (name "MANUFACTURER") "Vishay Semiconductor"))
      (libsource (lib "Altium Content Vault") (part "RES-2"))
    )
    (comp (ref "R49")
      (value "RC0805JR-1010KL")
      (footprint "RESC2013X60X35NL10T20")
      (fields (field (name "MANUFACTURER") "Yageo"))
      (libsource (lib "Altium Content Vault") (part "RES"))
    )
    (comp (ref "R50")
      (value "RC0603FR-0710KL")
      (footprint "FP-RC0603-0_55-IPC_C")
      (description "RES 10K OHM 1% 1/10W 0603")
      (fields (field (name "TOLERANCE") "1%"))
      (libsource (lib "Altium Content Vault") (part "1029c3af85768c4190bb7ad29bc67b5"))
    )
    (comp (ref "R52")
      (value "RN73C2A10KLTD")
      (footprint "FP-RN732A-MFG")
      (description "SMD Chip Resistor, Thin Film, 10.LKΩ, 100 V, 0805 [2012 Metric], 100 mW, 0.1%, RN73 Series")
      (fields
        (field (name "TOLERANCE") "42")
        (field (name "OCTOPART") "https://octopart.com/rn73c2a10kltd-te+connectivity-22738660")
      )
      (libsource (lib "Altium Content Vault") (part "1029c3af85768c4190bb7ad29bc67b5"))
    )
    (comp (ref "R53")
      (value "RT0805FRE07178RL")
      (footprint "FP-RT0805-MFG")
      (description "RES SMD 178 OHM 1% 1/8W 0805")
      (fields
        (field (name "TOLERANCE") "0.0001")
        (field (name "OCTOPART") "https://octopart.com/rt0805fre07178rl-yageo-1405991")
      )
      (libsource (lib "Altium Content Vault") (part "1029c3af85768c4190bb7ad29bc67b5"))
    )
    (comp (ref "R54")
      (value "RT0805FRE07178RL")
      (footprint "FP-RT0805-MFG")
      (description "RES SMD 178 OHM 1% 1/8W 0805")
      (fields
        (field (name "TOLERANCE") "0.0001")
        (field (name "OCTOPART") "https://octopart.com/rt0805fre07178rl-yageo-1405991")
      )
      (libsource (lib "Altium Content Vault") (part "1029c3af85768c4190bb7ad29bc67b5"))
    )
    (comp (ref "R55")
      (value "RN73C2A100KB")
      (footprint "FP-RN732A-MFG")
      (description "SMD Chip Resistor, Thin Film, 100KΩ, 100 V, 0805 [2012 Metric], 100 mW, 0.1%, RN73 Series")
      (fields
        (field (name "OCTOPART") "https://octopart.com/rn73c2a100kb-te+connectivity-16078029")
        (field (name "MANUFACTURER") "TE Connectivity")
      )
      (libsource (lib "Altium Content Vault") (part "1029c3af85768c4190bb7ad29bc67b5"))
    )
    (comp (ref "R57")
      (value "RT0603FRE1010KL")
      (footprint "FP-RT0603-MFG")
      (description "RT0603 10KΩ 0.1W 50 ppm/°C 1.00%")
      (fields
        (field (name "OCTOPART") "https://octopart.com/rt0603fre1010kl-yageo-26185585")
        (field (name "TOLERANCE") "0.01")
      )
      (libsource (lib "Altium Content Vault") (part "1029c3af85768c4190bb7ad29bc67b5"))
    )
    (comp (ref "R58")
      (value "RT0603FRE1010KL")
      (footprint "FP-RT0603-MFG")
      (description "RT0603 10KΩ 0.1W 50 ppm/°C 1.00%")
      (fields
        (field (name "OCTOPART") "https://octopart.com/rt0603fre1010kl-yageo-26185585")
        (field (name "TOLERANCE") "0.01")
      )
      (libsource (lib "Altium Content Vault") (part "1029c3af85768c4190bb7ad29bc67b5"))
    )
    (comp (ref "R70")
      (value "RT0603FRE1010KL")
      (footprint "FP-RT0603-MFG")
      (description "RT0603 10KΩ 0.1W 50 ppm/°C 1.00%")
      (fields
        (field (name "OCTOPART") "https://octopart.com/rt0603fre1010kl-yageo-26185585")
        (field (name "TOLERANCE") "0.01")
      )
      (libsource (lib "Altium Content Vault") (part "1029c3af85768c4190bb7ad29bc67b5"))
    )
    (comp (ref "R71")
      (value "RT0603FRE1010KL")
      (footprint "FP-RT0603-MFG")
      (description "RT0603 10KΩ 0.1W 50 ppm/°C 1.00%")
      (fields
        (field (name "OCTOPART") "https://octopart.com/rt0603fre1010kl-yageo-26185585")
        (field (name "TOLERANCE") "0.01")
      )
      (libsource (lib "Altium Content Vault") (part "1029c3af85768c4190bb7ad29bc67b5"))
    )
    (comp (ref "R72")
      (value "RT0603FRE1010KL")
      (footprint "FP-RT0603-MFG")
      (description "RT0603 10KΩ 0.1W 50 ppm/°C 1.00%")
      (fields
        (field (name "OCTOPART") "https://octopart.com/rt0603fre1010kl-yageo-26185585")
        (field (name "TOLERANCE") "0.01")
      )
      (libsource (lib "Altium Content Vault") (part "1029c3af85768c4190bb7ad29bc67b5"))
    )
    (comp (ref "R73")
      (value "RT0603FRE1010KL")
      (footprint "FP-RT0603-MFG")
      (description "RT0603 10KΩ 0.1W 50 ppm/°C 1.00%")
      (fields
        (field (name "OCTOPART") "https://octopart.com/rt0603fre1010kl-yageo-26185585")
        (field (name "TOLERANCE") "0.01")
      )
      (libsource (lib "Altium Content Vault") (part "1029c3af85768c4190bb7ad29bc67b5"))
    )
    (comp (ref "R74")
      (value "PLT0805Z5001AST5")
      (footprint "FP-PLT0805-MFG")
      (fields (field (name "TOLERANCE") "0.05%"))
      (libsource (lib "Altium Content Vault") (part "1029c3af85768c4190bb7ad29bc67b5"))
    )
    (comp (ref "R75")
      (value "PLT0805Z5001AST5")
      (footprint "FP-PLT0805-MFG")
      (fields (field (name "TOLERANCE") "0.05%"))
      (libsource (lib "Altium Content Vault") (part "1029c3af85768c4190bb7ad29bc67b5"))
    )
    (comp (ref "R76")
      (value "RT0603FRE1010KL")
      (footprint "FP-RT0603-MFG")
      (description "RT0603 10KΩ 0.1W 50 ppm/°C 1.00%")
      (fields
        (field (name "OCTOPART") "https://octopart.com/rt0603fre1010kl-yageo-26185585")
        (field (name "TOLERANCE") "0.01")
      )
      (libsource (lib "Altium Content Vault") (part "1029c3af85768c4190bb7ad29bc67b5"))
    )
    (comp (ref "R77")
      (value "RT0603FRE1010KL")
      (footprint "FP-RT0603-MFG")
      (description "RT0603 10KΩ 0.1W 50 ppm/°C 1.00%")
      (fields
        (field (name "OCTOPART") "https://octopart.com/rt0603fre1010kl-yageo-26185585")
        (field (name "TOLERANCE") "0.01")
      )
      (libsource (lib "Altium Content Vault") (part "1029c3af85768c4190bb7ad29bc67b5"))
    )
    (comp (ref "R78")
      (value "RT0805FRE07178RL")
      (footprint "FP-RT0805-MFG")
      (description "RES SMD 178 OHM 1% 1/8W 0805")
      (fields
        (field (name "TOLERANCE") "0.0001")
        (field (name "OCTOPART") "https://octopart.com/rt0805fre07178rl-yageo-1405991")
      )
      (libsource (lib "Altium Content Vault") (part "1029c3af85768c4190bb7ad29bc67b5"))
    )
    (comp (ref "R79")
      (value "RN73C2A100KB")
      (footprint "FP-RN732A-MFG")
      (description "SMD Chip Resistor, Thin Film, 100KΩ, 100 V, 0805 [2012 Metric], 100 mW, 0.1%, RN73 Series")
      (fields
        (field (name "OCTOPART") "https://octopart.com/rn73c2a100kb-te+connectivity-16078029")
        (field (name "MANUFACTURER") "TE Connectivity")
      )
      (libsource (lib "Altium Content Vault") (part "1029c3af85768c4190bb7ad29bc67b5"))
    )
    (comp (ref "R80")
      (value "RN73C2A10KLTD")
      (footprint "FP-RN732A-MFG")
      (description "SMD Chip Resistor, Thin Film, 10.LKΩ, 100 V, 0805 [2012 Metric], 100 mW, 0.1%, RN73 Series")
      (fields
        (field (name "TOLERANCE") "42")
        (field (name "OCTOPART") "https://octopart.com/rn73c2a10kltd-te+connectivity-22738660")
      )
      (libsource (lib "Altium Content Vault") (part "1029c3af85768c4190bb7ad29bc67b5"))
    )
    (comp (ref "R81")
      (value "RN73C2A100KB")
      (footprint "FP-RN732A-MFG")
      (description "SMD Chip Resistor, Thin Film, 100KΩ, 100 V, 0805 [2012 Metric], 100 mW, 0.1%, RN73 Series")
      (fields
        (field (name "OCTOPART") "https://octopart.com/rn73c2a100kb-te+connectivity-16078029")
        (field (name "MANUFACTURER") "TE Connectivity")
      )
      (libsource (lib "Altium Content Vault") (part "1029c3af85768c4190bb7ad29bc67b5"))
    )
    (comp (ref "R82")
      (value "RN73C2A10KLTD")
      (footprint "FP-RN732A-MFG")
      (description "SMD Chip Resistor, Thin Film, 10.LKΩ, 100 V, 0805 [2012 Metric], 100 mW, 0.1%, RN73 Series")
      (fields
        (field (name "TOLERANCE") "42")
        (field (name "OCTOPART") "https://octopart.com/rn73c2a10kltd-te+connectivity-22738660")
      )
      (libsource (lib "Altium Content Vault") (part "1029c3af85768c4190bb7ad29bc67b5"))
    )
    (comp (ref "R83")
      (value "RN73C2A10KLTD")
      (footprint "FP-RN732A-MFG")
      (description "SMD Chip Resistor, Thin Film, 10.LKΩ, 100 V, 0805 [2012 Metric], 100 mW, 0.1%, RN73 Series")
      (fields
        (field (name "TOLERANCE") "42")
        (field (name "OCTOPART") "https://octopart.com/rn73c2a10kltd-te+connectivity-22738660")
      )
      (libsource (lib "Altium Content Vault") (part "1029c3af85768c4190bb7ad29bc67b5"))
    )
    (comp (ref "R99")
      (value "RC0805JR-1010KL")
      (footprint "RESC2013X60X35NL10T20")
      (fields (field (name "MANUFACTURER") "Yageo"))
      (libsource (lib "Altium Content Vault") (part "RES"))
    )
    (comp (ref "SW1")
      (value "25136NAB")
      (footprint "FP-25136NAB-MFG")
      (description "SWITCH SLIDE SPDT 4A 125V")
      (libsource (lib "Altium Content Vault") (part "5e517060f043dec04dd44aead8b4f3e"))
    )
    (comp (ref "SW2")
      (value "25136NAB")
      (footprint "FP-25136NAB-MFG")
      (description "SWITCH SLIDE SPDT 4A 125V")
      (libsource (lib "Altium Content Vault") (part "5e517060f043dec04dd44aead8b4f3e"))
    )
    (comp (ref "S_gnd1")
      (value "Through hole")
      (footprint "Through hole")
      (libsource (lib "Schlib") (part "Through hole"))
    )
    (comp (ref "S_gnd2")
      (value "Through hole")
      (footprint "Through hole")
      (libsource (lib "Schlib") (part "Through hole"))
    )
    (comp (ref "U1")
      (value "LM358AP")
      (footprint "P0008A")
      (description "Dual Operational Amplifier, 3 to 32 V, 0 to 70 degC, 8-Pin PDIP (P), Pb-Free (RoHS), Tube")
      (libsource (lib "Altium Content Vault") (part "TI-LM358-8"))
    )
    (comp (ref "U2")
      (value "LM358AP")
      (footprint "P0008A")
      (description "Dual Operational Amplifier, 3 to 32 V, 0 to 70 degC, 8-Pin PDIP (P), Pb-Free (RoHS), Tube")
      (libsource (lib "Altium Content Vault") (part "TI-LM358-8"))
    )
    (comp (ref "U3")
      (value "LM358AP")
      (footprint "P0008A")
      (description "Dual Operational Amplifier, 3 to 32 V, 0 to 70 degC, 8-Pin PDIP (P), Pb-Free (RoHS), Tube")
      (libsource (lib "Altium Content Vault") (part "TI-LM358-8"))
    )
    (comp (ref "U4")
      (value "LM358AP")
      (footprint "P0008A")
      (description "Dual Operational Amplifier, 3 to 32 V, 0 to 70 degC, 8-Pin PDIP (P), Pb-Free (RoHS), Tube")
      (libsource (lib "Altium Content Vault") (part "TI-LM358-8"))
    )
    (comp (ref "U5")
      (value "L7812ABD2T-TR")
      (footprint "TO-263_L")
      (description "Positive Voltage Regulator, 3-Pin D2PAK, Tape and Reel")
      (libsource (lib "Altium Content Vault") (part "PM-REG-L4940-SOT3"))
    )
    (comp (ref "U6")
      (value "LM7912CT")
      (footprint "NDE0003A")
      (description "3-Terminal Negative Regulator, 3-pin TO-220")
      (fields (field (name "MANUFACTURER") "Texas Instruments"))
      (libsource (lib "Altium Content Vault") (part "PM-REG-LM7905-SIL3"))
    )
    (comp (ref "U7")
      (value "LM358AP")
      (footprint "P0008A")
      (description "Dual Operational Amplifier, 3 to 32 V, 0 to 70 degC, 8-Pin PDIP (P), Pb-Free (RoHS), Tube")
      (libsource (lib "Altium Content Vault") (part "TI-LM358-8"))
    )
    (comp (ref "U8")
      (value "LM358AP")
      (footprint "P0008A")
      (description "Dual Operational Amplifier, 3 to 32 V, 0 to 70 degC, 8-Pin PDIP (P), Pb-Free (RoHS), Tube")
      (libsource (lib "Altium Content Vault") (part "TI-LM358-8"))
    )
    (comp (ref "U9")
      (value "LM358AP")
      (footprint "P0008A")
      (description "Dual Operational Amplifier, 3 to 32 V, 0 to 70 degC, 8-Pin PDIP (P), Pb-Free (RoHS), Tube")
      (libsource (lib "Altium Content Vault") (part "TI-LM358-8"))
    )
    (comp (ref "U10")
      (value "LM358AP")
      (footprint "P0008A")
      (description "Dual Operational Amplifier, 3 to 32 V, 0 to 70 degC, 8-Pin PDIP (P), Pb-Free (RoHS), Tube")
      (libsource (lib "Altium Content Vault") (part "TI-LM358-8"))
    )
    (comp (ref "U11")
      (value "UA741CP")
      (footprint "P0008A")
      (description "General-Purpose Operational Amplifier, 7 to 36 V, 0 to 70 degC, 8-pin DIP (P8), Pb-Free (RoHS)")
      (fields (field (name "MANUFACTURER") "Texas Instruments"))
      (libsource (lib "Altium Content Vault") (part "TI-AMP-S5-2-8"))
    )
    (comp (ref "U13")
      (value "UA741CP")
      (footprint "P0008A")
      (description "General-Purpose Operational Amplifier, 7 to 36 V, 0 to 70 degC, 8-pin DIP (P8), Pb-Free (RoHS)")
      (fields (field (name "MANUFACTURER") "Texas Instruments"))
      (libsource (lib "Altium Content Vault") (part "TI-AMP-S5-2-8"))
    )
    (comp (ref "U14")
      (value "UA741CP")
      (footprint "P0008A")
      (description "General-Purpose Operational Amplifier, 7 to 36 V, 0 to 70 degC, 8-pin DIP (P8), Pb-Free (RoHS)")
      (fields (field (name "MANUFACTURER") "Texas Instruments"))
      (libsource (lib "Altium Content Vault") (part "TI-AMP-S5-2-8"))
    )
    (comp (ref "U19")
      (value "UA741CP")
      (footprint "P0008A")
      (description "General-Purpose Operational Amplifier, 7 to 36 V, 0 to 70 degC, 8-pin DIP (P8), Pb-Free (RoHS)")
      (fields (field (name "MANUFACTURER") "Texas Instruments"))
      (libsource (lib "Altium Content Vault") (part "TI-AMP-S5-2-8"))
    )
    (comp (ref "U20")
      (value "UA741CP")
      (footprint "P0008A")
      (description "General-Purpose Operational Amplifier, 7 to 36 V, 0 to 70 degC, 8-pin DIP (P8), Pb-Free (RoHS)")
      (fields (field (name "MANUFACTURER") "Texas Instruments"))
      (libsource (lib "Altium Content Vault") (part "TI-AMP-S5-2-8"))
    )
    (comp (ref "U21")
      (value "UA741CP")
      (footprint "P0008A")
      (description "General-Purpose Operational Amplifier, 7 to 36 V, 0 to 70 degC, 8-pin DIP (P8), Pb-Free (RoHS)")
      (fields (field (name "MANUFACTURER") "Texas Instruments"))
      (libsource (lib "Altium Content Vault") (part "TI-AMP-S5-2-8"))
    )
    (comp (ref "U22")
      (value "UA741CP")
      (footprint "P0008A")
      (description "General-Purpose Operational Amplifier, 7 to 36 V, 0 to 70 degC, 8-pin DIP (P8), Pb-Free (RoHS)")
      (fields (field (name "MANUFACTURER") "Texas Instruments"))
      (libsource (lib "Altium Content Vault") (part "TI-AMP-S5-2-8"))
    )
    (comp (ref "U32")
      (value "LM318M/NOPB")
      (footprint "D0008A_M")
      (description "Operational Amplifier, 8-pin Narrow SOIC, Pb-Free")
      (fields (field (name "MANUFACTURER") "Texas Instruments"))
      (libsource (lib "Altium Content Vault") (part "AMP-OPA-LM118-8"))
    )
    (comp (ref "U33")
      (value "LM318M/NOPB")
      (footprint "D0008A_M")
      (description "Operational Amplifier, 8-pin Narrow SOIC, Pb-Free")
      (fields (field (name "MANUFACTURER") "Texas Instruments"))
      (libsource (lib "Altium Content Vault") (part "AMP-OPA-LM118-8"))
    )
    (comp (ref "U34")
      (value "LM318M/NOPB")
      (footprint "D0008A_M")
      (description "Operational Amplifier, 8-pin Narrow SOIC, Pb-Free")
      (fields (field (name "MANUFACTURER") "Texas Instruments"))
      (libsource (lib "Altium Content Vault") (part "AMP-OPA-LM118-8"))
    )
    (comp (ref "U39")
      (value "LM2596S-5.0/NOPB")
      (footprint "KTT0005B_M")
      (description "SIMPLE SWITCHER® Power Converter 150 KHz 3A Step-Down Voltage Regulator, 5-pin TO-263, Pb-Free")
      (fields (field (name "MANUFACTURER") "Texas Instruments"))
      (libsource (lib "Altium Content Vault") (part "PM-REG-LM2575HVS-12"))
    )
    (comp (ref "VR1")
      (value "TC33X-2-203E")
      (footprint "TRIM_TC33X-2-203E")
      (description "20 kOhms 0.1W, 1/10W J Lead Surface Mount Trimmer Potentiometer Cermet 1 Turn Top Adjustment")
      (fields (field (name "MF") "Bourns") (field (name "DIGI-KEY_PART_NUMBER") "TC33X-2-203ECT-ND"))
      (libsource (lib "TC33X-2-203E") (part "TC33X-2-203E"))
    )
  )
  (nets
    (net (code "1") (name "+5") (class "Default")
      (node (ref "C97") (pin "1") (pinfunction "P_1") (pintype "passive"))
      (node (ref "L5") (pin "1") (pinfunction "1_1") (pintype "passive"))
      (node (ref "R82") (pin "2") (pinfunction "2_2") (pintype "passive"))
      (node (ref "R83") (pin "2") (pinfunction "2_2") (pintype "passive"))
      (node (ref "U39") (pin "4") (pinfunction "FB_4") (pintype "input"))
    )
    (net (code "2") (name "+12") (class "Default")
      (node (ref "12V") (pin "1") (pinfunction "port_1") (pintype "passive"))
      (node (ref "C1") (pin "2") (pinfunction "2_2") (pintype "passive"))
      (node (ref "C12") (pin "2") (pinfunction "2_2") (pintype "passive"))
      (node (ref "C21") (pin "1") (pinfunction "1_1") (pintype "passive"))
      (node (ref "C27") (pin "1") (pinfunction "1_1") (pintype "passive"))
      (node (ref "C3") (pin "2") (pinfunction "2_2") (pintype "passive"))
      (node (ref "C30") (pin "1") (pinfunction "1_1") (pintype "passive"))
      (node (ref "C31") (pin "1") (pinfunction "1_1") (pintype "passive"))
      (node (ref "C33") (pin "1") (pinfunction "1_1") (pintype "passive"))
      (node (ref "C35") (pin "1") (pinfunction "1_1") (pintype "passive"))
      (node (ref "C37") (pin "1") (pinfunction "1_1") (pintype "passive"))
      (node (ref "C5") (pin "1") (pinfunction "1_1") (pintype "passive"))
      (node (ref "C60") (pin "2") (pinfunction "2_2") (pintype "passive"))
      (node (ref "C63") (pin "1") (pinfunction "1_1") (pintype "passive"))
      (node (ref "C65") (pin "1") (pinfunction "1_1") (pintype "passive"))
      (node (ref "C66") (pin "1") (pinfunction "1_1") (pintype "passive"))
      (node (ref "C68") (pin "1") (pinfunction "1_1") (pintype "passive"))
      (node (ref "C7") (pin "1") (pinfunction "1_1") (pintype "passive"))
      (node (ref "C70") (pin "1") (pinfunction "1_1") (pintype "passive"))
      (node (ref "C9") (pin "1") (pinfunction "1_1") (pintype "passive"))
      (node (ref "C96") (pin "1") (pinfunction "P_1") (pintype "passive"))
      (node (ref "J3") (pin "1") (pinfunction "1_1") (pintype "passive"))
      (node (ref "J4") (pin "2") (pinfunction "2_2") (pintype "passive"))
      (node (ref "Q2") (pin "2") (pinfunction "D_2") (pintype "passive"))
      (node (ref "SW1") (pin "1") (pinfunction "1_1") (pintype "passive"))
      (node (ref "U1") (pin "8") (pinfunction "VCC_8") (pintype "power_in"))
      (node (ref "U10") (pin "8") (pinfunction "VCC_8") (pintype "power_in"))
      (node (ref "U11") (pin "7") (pinfunction "VCC+_7") (pintype "power_in"))
      (node (ref "U13") (pin "7") (pinfunction "VCC+_7") (pintype "power_in"))
      (node (ref "U14") (pin "7") (pinfunction "VCC+_7") (pintype "power_in"))
      (node (ref "U19") (pin "7") (pinfunction "VCC+_7") (pintype "power_in"))
      (node (ref "U2") (pin "8") (pinfunction "VCC_8") (pintype "power_in"))
      (node (ref "U20") (pin "7") (pinfunction "VCC+_7") (pintype "power_in"))
      (node (ref "U21") (pin "7") (pinfunction "VCC+_7") (pintype "power_in"))
      (node (ref "U22") (pin "7") (pinfunction "VCC+_7") (pintype "power_in"))
      (node (ref "U3") (pin "8") (pinfunction "VCC_8") (pintype "power_in"))
      (node (ref "U32") (pin "7") (pinfunction "V+_7") (pintype "power_in"))
      (node (ref "U33") (pin "7") (pinfunction "V+_7") (pintype "power_in"))
      (node (ref "U34") (pin "7") (pinfunction "V+_7") (pintype "power_in"))
      (node (ref "U39") (pin "1") (pinfunction "VIN_1") (pintype "power_in"))
      (node (ref "U4") (pin "8") (pinfunction "VCC_8") (pintype "power_in"))
      (node (ref "U5") (pin "3") (pinfunction "OUT_3") (pintype "power_in"))
      (node (ref "U7") (pin "8") (pinfunction "VCC_8") (pintype "power_in"))
      (node (ref "U8") (pin "8") (pinfunction "VCC_8") (pintype "power_in"))
      (node (ref "U9") (pin "8") (pinfunction "VCC_8") (pintype "power_in"))
    )
    (net (code "3") (name "-12") (class "Default")
      (node (ref "C10") (pin "1") (pinfunction "1_1") (pintype "passive"))
      (node (ref "C14") (pin "1") (pinfunction "C_1") (pintype "passive"))
      (node (ref "C2") (pin "1") (pinfunction "1_1") (pintype "passive"))
      (node (ref "C22") (pin "2") (pinfunction "2_2") (pintype "passive"))
      (node (ref "C28") (pin "1") (pinfunction "1_1") (pintype "passive"))
      (node (ref "C29") (pin "1") (pinfunction "1_1") (pintype "passive"))
      (node (ref "C32") (pin "1") (pinfunction "1_1") (pintype "passive"))
      (node (ref "C34") (pin "2") (pinfunction "2_2") (pintype "passive"))
      (node (ref "C36") (pin "1") (pinfunction "1_1") (pintype "passive"))
      (node (ref "C38") (pin "1") (pinfunction "1_1") (pintype "passive"))
      (node (ref "C4") (pin "1") (pinfunction "1_1") (pintype "passive"))
      (node (ref "C59") (pin "1") (pinfunction "1_1") (pintype "passive"))
      (node (ref "C6") (pin "1") (pinfunction "1_1") (pintype "passive"))
      (node (ref "C61") (pin "2") (pinfunction "2_2") (pintype "passive"))
      (node (ref "C64") (pin "2") (pinfunction "2_2") (pintype "passive"))
      (node (ref "C67") (pin "1") (pinfunction "1_1") (pintype "passive"))
      (node (ref "C69") (pin "1") (pinfunction "1_1") (pintype "passive"))
      (node (ref "C71") (pin "1") (pinfunction "1_1") (pintype "passive"))
      (node (ref "C8") (pin "1") (pinfunction "1_1") (pintype "passive"))
      (node (ref "SW2") (pin "1") (pinfunction "1_1") (pintype "passive"))
      (node (ref "U1") (pin "4") (pinfunction "GND_4") (pintype "power_in"))
      (node (ref "U10") (pin "4") (pinfunction "GND_4") (pintype "power_in"))
      (node (ref "U11") (pin "4") (pinfunction "VCC-_4") (pintype "power_in"))
      (node (ref "U13") (pin "4") (pinfunction "VCC-_4") (pintype "power_in"))
      (node (ref "U14") (pin "4") (pinfunction "VCC-_4") (pintype "power_in"))
      (node (ref "U19") (pin "4") (pinfunction "VCC-_4") (pintype "power_in"))
      (node (ref "U2") (pin "4") (pinfunction "GND_4") (pintype "power_in"))
      (node (ref "U20") (pin "4") (pinfunction "VCC-_4") (pintype "power_in"))
      (node (ref "U21") (pin "4") (pinfunction "VCC-_4") (pintype "power_in"))
      (node (ref "U22") (pin "4") (pinfunction "VCC-_4") (pintype "power_in"))
      (node (ref "U3") (pin "4") (pinfunction "GND_4") (pintype "power_in"))
      (node (ref "U32") (pin "4") (pinfunction "V-_4") (pintype "power_in"))
      (node (ref "U33") (pin "4") (pinfunction "V-_4") (pintype "power_in"))
      (node (ref "U34") (pin "4") (pinfunction "V-_4") (pintype "power_in"))
      (node (ref "U4") (pin "4") (pinfunction "GND_4") (pintype "power_in"))
      (node (ref "U6") (pin "3") (pinfunction "OUT_3") (pintype "power_in"))
      (node (ref "U7") (pin "4") (pinfunction "GND_4") (pintype "power_in"))
      (node (ref "U8") (pin "4") (pinfunction "GND_4") (pintype "power_in"))
      (node (ref "U9") (pin "4") (pinfunction "GND_4") (pintype "power_in"))
    )
    (net (code "4") (name "/Error") (class "Default")
      (node (ref "C24") (pin "1") (pinfunction "1_1") (pintype "passive"))
      (node (ref "J11") (pin "2") (pinfunction "2_2") (pintype "passive"))
      (node (ref "J5") (pin "1") (pinfunction "1_1") (pintype "passive"))
      (node (ref "R36") (pin "1") (pinfunction "1_1") (pintype "passive"))
      (node (ref "U22") (pin "6") (pinfunction "OUT_6") (pintype "output"))
    )
    (net (code "5") (name "/PID") (class "Default")
      (node (ref "R35") (pin "1") (pinfunction "1_1") (pintype "passive"))
      (node (ref "R58") (pin "1") (pinfunction "1_1") (pintype "passive"))
      (node (ref "R72") (pin "1") (pinfunction "1_1") (pintype "passive"))
      (node (ref "U10") (pin "1") (pinfunction "1OUT_1") (pintype "output"))
      (node (ref "U33") (pin "2") (pinfunction "IN-_2") (pintype "input"))
      (node (ref "U34") (pin "3") (pinfunction "IN+_3") (pintype "input"))
    )
    (net (code "6") (name "/PID_out") (class "Default")
      (node (ref "R77") (pin "2") (pinfunction "2_2") (pintype "passive"))
      (node (ref "U32") (pin "3") (pinfunction "IN+_3") (pintype "input"))
      (node (ref "U4") (pin "1") (pinfunction "1OUT_1") (pintype "output"))
    )
    (net (code "7") (name "/TRI") (class "Default")
      (node (ref "J12") (pin "1") (pinfunction "1_1") (pintype "passive"))
      (node (ref "R57") (pin "1") (pinfunction "1_1") (pintype "passive"))
      (node (ref "R70") (pin "1") (pinfunction "1_1") (pintype "passive"))
      (node (ref "U21") (pin "6") (pinfunction "OUT_6") (pintype "output"))
    )
    (net (code "8") (name "/Tri_out") (class "Default")
      (node (ref "R76") (pin "2") (pinfunction "2_2") (pintype "passive"))
      (node (ref "U3") (pin "1") (pinfunction "1OUT_1") (pintype "output"))
      (node (ref "U32") (pin "2") (pinfunction "IN-_2") (pintype "input"))
    )
    (net (code "9") (name "/VBB+") (class "Default")
      (node (ref "C11") (pin "2") (pinfunction "2_2") (pintype "passive"))
      (node (ref "SW1") (pin "3") (pinfunction "3_3") (pintype "passive"))
      (node (ref "U5") (pin "1") (pinfunction "IN_1") (pintype "power_in"))
    )
    (net (code "10") (name "/VBB-") (class "Default")
      (node (ref "C13") (pin "2") (pinfunction "2_2") (pintype "passive"))
      (node (ref "SW2") (pin "3") (pinfunction "3_3") (pintype "passive"))
      (node (ref "U6") (pin "2") (pinfunction "IN_2") (pintype "power_in"))
    )
    (net (code "11") (name "GND") (class "Default")
      (node (ref "C1") (pin "1") (pinfunction "1_1") (pintype "passive"))
      (node (ref "C10") (pin "2") (pinfunction "2_2") (pintype "passive"))
      (node (ref "C11") (pin "1") (pinfunction "1_1") (pintype "passive"))
      (node (ref "C12") (pin "1") (pinfunction "1_1") (pintype "passive"))
      (node (ref "C13") (pin "1") (pinfunction "1_1") (pintype "passive"))
      (node (ref "C14") (pin "2") (pinfunction "A_2") (pintype "passive"))
      (node (ref "C2") (pin "2") (pinfunction "2_2") (pintype "passive"))
      (node (ref "C21") (pin "2") (pinfunction "2_2") (pintype "passive"))
      (node (ref "C22") (pin "1") (pinfunction "1_1") (pintype "passive"))
      (node (ref "C27") (pin "2") (pinfunction "2_2") (pintype "passive"))
      (node (ref "C28") (pin "2") (pinfunction "2_2") (pintype "passive"))
      (node (ref "C29") (pin "2") (pinfunction "2_2") (pintype "passive"))
      (node (ref "C3") (pin "1") (pinfunction "1_1") (pintype "passive"))
      (node (ref "C30") (pin "2") (pinfunction "2_2") (pintype "passive"))
      (node (ref "C31") (pin "2") (pinfunction "2_2") (pintype "passive"))
      (node (ref "C32") (pin "2") (pinfunction "2_2") (pintype "passive"))
      (node (ref "C33") (pin "2") (pinfunction "2_2") (pintype "passive"))
      (node (ref "C34") (pin "1") (pinfunction "1_1") (pintype "passive"))
      (node (ref "C35") (pin "2") (pinfunction "2_2") (pintype "passive"))
      (node (ref "C36") (pin "2") (pinfunction "2_2") (pintype "passive"))
      (node (ref "C37") (pin "2") (pinfunction "2_2") (pintype "passive"))
      (node (ref "C38") (pin "2") (pinfunction "2_2") (pintype "passive"))
      (node (ref "C4") (pin "2") (pinfunction "2_2") (pintype "passive"))
      (node (ref "C5") (pin "2") (pinfunction "2_2") (pintype "passive"))
      (node (ref "C59") (pin "2") (pinfunction "2_2") (pintype "passive"))
      (node (ref "C6") (pin "2") (pinfunction "2_2") (pintype "passive"))
      (node (ref "C60") (pin "1") (pinfunction "1_1") (pintype "passive"))
      (node (ref "C61") (pin "1") (pinfunction "1_1") (pintype "passive"))
      (node (ref "C63") (pin "2") (pinfunction "2_2") (pintype "passive"))
      (node (ref "C64") (pin "1") (pinfunction "1_1") (pintype "passive"))
      (node (ref "C65") (pin "2") (pinfunction "2_2") (pintype "passive"))
      (node (ref "C66") (pin "2") (pinfunction "2_2") (pintype "passive"))
      (node (ref "C67") (pin "2") (pinfunction "2_2") (pintype "passive"))
      (node (ref "C68") (pin "2") (pinfunction "2_2") (pintype "passive"))
      (node (ref "C69") (pin "2") (pinfunction "2_2") (pintype "passive"))
      (node (ref "C7") (pin "2") (pinfunction "2_2") (pintype "passive"))
      (node (ref "C70") (pin "2") (pinfunction "2_2") (pintype "passive"))
      (node (ref "C71") (pin "2") (pinfunction "2_2") (pintype "passive"))
      (node (ref "C8") (pin "2") (pinfunction "2_2") (pintype "passive"))
      (node (ref "C9") (pin "2") (pinfunction "2_2") (pintype "passive"))
      (node (ref "C96") (pin "2") (pinfunction "N_2") (pintype "passive"))
      (node (ref "C97") (pin "2") (pinfunction "N_2") (pintype "passive"))
      (node (ref "D13") (pin "A") (pinfunction "A_A") (pintype "passive"))
      (node (ref "Q3") (pin "3") (pinfunction "S_3") (pintype "passive"))
      (node (ref "Q4") (pin "3") (pinfunction "S_3") (pintype "passive"))
      (node (ref "R30") (pin "1") (pinfunction "1_1") (pintype "passive"))
      (node (ref "R31") (pin "1") (pinfunction "1_1") (pintype "passive"))
      (node (ref "R32") (pin "1") (pinfunction "1_1") (pintype "passive"))
      (node (ref "R40") (pin "1") (pinfunction "1_1") (pintype "passive"))
      (node (ref "R41") (pin "2") (pinfunction "2_2") (pintype "passive"))
      (node (ref "R42") (pin "1") (pinfunction "1_1") (pintype "passive"))
      (node (ref "R52") (pin "1") (pinfunction "1_1") (pintype "passive"))
      (node (ref "R55") (pin "1") (pinfunction "1_1") (pintype "passive"))
      (node (ref "R79") (pin "1") (pinfunction "1_1") (pintype "passive"))
      (node (ref "R80") (pin "1") (pinfunction "1_1") (pintype "passive"))
      (node (ref "R81") (pin "1") (pinfunction "1_1") (pintype "passive"))
      (node (ref "R99") (pin "1") (pinfunction "1_1") (pintype "passive"))
      (node (ref "S_gnd1") (pin "1") (pinfunction "port_1") (pintype "passive"))
      (node (ref "S_gnd2") (pin "1") (pinfunction "port_1") (pintype "passive"))
      (node (ref "U1") (pin "3") (pinfunction "1IN+_3") (pintype "input"))
      (node (ref "U10") (pin "3") (pinfunction "1IN+_3") (pintype "input"))
      (node (ref "U2") (pin "3") (pinfunction "1IN+_3") (pintype "input"))
      (node (ref "U21") (pin "3") (pinfunction "IN+_3") (pintype "input"))
      (node (ref "U22") (pin "3") (pinfunction "IN+_3") (pintype "input"))
      (node (ref "U3") (pin "3") (pinfunction "1IN+_3") (pintype "input"))
      (node (ref "U33") (pin "3") (pinfunction "IN+_3") (pintype "input"))
      (node (ref "U34") (pin "2") (pinfunction "IN-_2") (pintype "input"))
      (node (ref "U39") (pin "3") (pinfunction "GND_3") (pintype "power_in"))
      (node (ref "U39") (pin "5") (pinfunction "~{ON}/OFF_5") (pintype "input"))
      (node (ref "U39") (pin "6") (pinfunction "TAB_6") (pintype "power_in"))
      (node (ref "U4") (pin "3") (pinfunction "1IN+_3") (pintype "input"))
      (node (ref "U5") (pin "4") (pinfunction "GND_4") (pintype "power_in"))
      (node (ref "U6") (pin "1") (pinfunction "GND_1") (pintype "power_in"))
      (node (ref "U7") (pin "3") (pinfunction "1IN+_3") (pintype "input"))
      (node (ref "U9") (pin "3") (pinfunction "1IN+_3") (pintype "input"))
    )
    (net (code "12") (name "Net-(C23-Pad2)") (class "Default")
      (node (ref "C23") (pin "2") (pinfunction "2_2") (pintype "passive"))
      (node (ref "R39") (pin "2") (pinfunction "2_2") (pintype "passive"))
    )
    (net (code "13") (name "Net-(C62-Pad2)") (class "Default")
      (node (ref "C62") (pin "2") (pinfunction "2_2") (pintype "passive"))
      (node (ref "R49") (pin "2") (pinfunction "2_2") (pintype "passive"))
    )
    (net (code "14") (name "Net-(D5-A)") (class "Default")
      (node (ref "D5") (pin "2") (pinfunction "A_2") (pintype "passive"))
      (node (ref "D7") (pin "1") (pinfunction "C_1") (pintype "passive"))
      (node (ref "U1") (pin "1") (pinfunction "1OUT_1") (pintype "output"))
    )
    (net (code "15") (name "Net-(D5-C)") (class "Default")
      (node (ref "D5") (pin "1") (pinfunction "C_1") (pintype "passive"))
      (node (ref "R57") (pin "2") (pinfunction "2_2") (pintype "passive"))
      (node (ref "R71") (pin "1") (pinfunction "1_1") (pintype "passive"))
      (node (ref "U1") (pin "2") (pinfunction "1IN-_2") (pintype "input"))
    )
    (net (code "16") (name "Net-(D6-A)") (class "Default")
      (node (ref "D6") (pin "2") (pinfunction "A_2") (pintype "passive"))
      (node (ref "D8") (pin "1") (pinfunction "C_1") (pintype "passive"))
      (node (ref "U2") (pin "1") (pinfunction "1OUT_1") (pintype "output"))
    )
    (net (code "17") (name "Net-(D6-C)") (class "Default")
      (node (ref "D6") (pin "1") (pinfunction "C_1") (pintype "passive"))
      (node (ref "R58") (pin "2") (pinfunction "2_2") (pintype "passive"))
      (node (ref "R73") (pin "1") (pinfunction "1_1") (pintype "passive"))
      (node (ref "U2") (pin "2") (pinfunction "1IN-_2") (pintype "input"))
    )
    (net (code "18") (name "Net-(D7-A)") (class "Default")
      (node (ref "D7") (pin "2") (pinfunction "A_2") (pintype "passive"))
      (node (ref "R71") (pin "2") (pinfunction "2_2") (pintype "passive"))
      (node (ref "R74") (pin "1") (pinfunction "1_1") (pintype "passive"))
    )
    (net (code "19") (name "Net-(D8-A)") (class "Default")
      (node (ref "D8") (pin "2") (pinfunction "A_2") (pintype "passive"))
      (node (ref "R73") (pin "2") (pinfunction "2_2") (pintype "passive"))
      (node (ref "R75") (pin "1") (pinfunction "1_1") (pintype "passive"))
    )
    (net (code "20") (name "Net-(D13-K)") (class "Default")
      (node (ref "D13") (pin "C") (pinfunction "K_C") (pintype "passive"))
      (node (ref "L5") (pin "2") (pinfunction "2_2") (pintype "passive"))
      (node (ref "U39") (pin "2") (pinfunction "OUT_2") (pintype "power_in"))
    )
    (net (code "21") (name "Net-(ENA-port)") (class "Default")
      (node (ref "ENA") (pin "1") (pinfunction "port_1") (pintype "passive"))
      (node (ref "R52") (pin "2") (pinfunction "2_2") (pintype "passive"))
      (node (ref "VR1") (pin "1") (pinfunction "CCW_1") (pintype "passive"))
    )
    (net (code "22") (name "Net-(In1-port)") (class "Default")
      (node (ref "In1") (pin "1") (pinfunction "port_1") (pintype "passive"))
      (node (ref "Q4") (pin "2") (pinfunction "D_2") (pintype "passive"))
      (node (ref "R82") (pin "1") (pinfunction "1_1") (pintype "passive"))
    )
    (net (code "23") (name "Net-(In2-port)") (class "Default")
      (node (ref "In2") (pin "1") (pinfunction "port_1") (pintype "passive"))
      (node (ref "Q3") (pin "2") (pinfunction "D_2") (pintype "passive"))
      (node (ref "R83") (pin "1") (pinfunction "1_1") (pintype "passive"))
    )
    (net (code "24") (name "Net-(Q2-G)") (class "Default")
      (node (ref "Q2") (pin "1") (pinfunction "G_1") (pintype "passive"))
      (node (ref "R78") (pin "2") (pinfunction "2_2") (pintype "passive"))
      (node (ref "R79") (pin "2") (pinfunction "2_2") (pintype "passive"))
    )
    (net (code "25") (name "Net-(Q2-S)") (class "Default")
      (node (ref "Q2") (pin "3") (pinfunction "S_3") (pintype "passive"))
      (node (ref "R80") (pin "2") (pinfunction "2_2") (pintype "passive"))
      (node (ref "VR1") (pin "2") (pinfunction "W_2") (pintype "passive"))
    )
    (net (code "26") (name "Net-(Q3-G)") (class "Default")
      (node (ref "Q3") (pin "1") (pinfunction "G_1") (pintype "passive"))
      (node (ref "R53") (pin "2") (pinfunction "2_2") (pintype "passive"))
      (node (ref "R55") (pin "2") (pinfunction "2_2") (pintype "passive"))
    )
    (net (code "27") (name "Net-(Q4-G)") (class "Default")
      (node (ref "Q4") (pin "1") (pinfunction "G_1") (pintype "passive"))
      (node (ref "R54") (pin "2") (pinfunction "2_2") (pintype "passive"))
      (node (ref "R81") (pin "2") (pinfunction "2_2") (pintype "passive"))
    )
    (net (code "28") (name "Net-(R46-Pad2)") (class "Default")
      (node (ref "R46") (pin "2") (pinfunction "2_2") (pintype "passive"))
      (node (ref "R48") (pin "1") (pinfunction "1_1") (pintype "passive"))
    )
    (net (code "29") (name "Net-(U3A-1IN-)") (class "Default")
      (node (ref "R70") (pin "2") (pinfunction "2_2") (pintype "passive"))
      (node (ref "R74") (pin "2") (pinfunction "2_2") (pintype "passive"))
      (node (ref "R76") (pin "1") (pinfunction "1_1") (pintype "passive"))
      (node (ref "U3") (pin "2") (pinfunction "1IN-_2") (pintype "input"))
    )
    (net (code "30") (name "Net-(U4A-1IN-)") (class "Default")
      (node (ref "R72") (pin "2") (pinfunction "2_2") (pintype "passive"))
      (node (ref "R75") (pin "2") (pinfunction "2_2") (pintype "passive"))
      (node (ref "R77") (pin "1") (pinfunction "1_1") (pintype "passive"))
      (node (ref "U4") (pin "2") (pinfunction "1IN-_2") (pintype "input"))
    )
    (net (code "31") (name "Net-(U7A-1IN-)") (class "Default")
      (node (ref "C25") (pin "1") (pinfunction "1_1") (pintype "passive"))
      (node (ref "J11") (pin "1") (pinfunction "1_1") (pintype "passive"))
      (node (ref "R45") (pin "1") (pinfunction "1_1") (pintype "passive"))
      (node (ref "U7") (pin "2") (pinfunction "1IN-_2") (pintype "input"))
    )
    (net (code "32") (name "Net-(U7A-1OUT)") (class "Default")
      (node (ref "C25") (pin "2") (pinfunction "2_2") (pintype "passive"))
      (node (ref "J7") (pin "2") (pinfunction "2_2") (pintype "passive"))
      (node (ref "R45") (pin "2") (pinfunction "2_2") (pintype "passive"))
      (node (ref "U7") (pin "1") (pinfunction "1OUT_1") (pintype "output"))
    )
    (net (code "33") (name "Net-(U8A-1IN+)") (class "Default")
      (node (ref "R40") (pin "2") (pinfunction "2_2") (pintype "passive"))
      (node (ref "U8") (pin "3") (pinfunction "1IN+_3") (pintype "input"))
    )
    (net (code "34") (name "Net-(U8A-1IN-)") (class "Default")
      (node (ref "R36") (pin "2") (pinfunction "2_2") (pintype "passive"))
      (node (ref "R46") (pin "1") (pinfunction "1_1") (pintype "passive"))
      (node (ref "U8") (pin "2") (pinfunction "1IN-_2") (pintype "input"))
    )
    (net (code "35") (name "Net-(U8A-1OUT)") (class "Default")
      (node (ref "J6") (pin "2") (pinfunction "2_2") (pintype "passive"))
      (node (ref "R48") (pin "2") (pinfunction "2_2") (pintype "passive"))
      (node (ref "U8") (pin "1") (pinfunction "1OUT_1") (pintype "output"))
    )
    (net (code "36") (name "Net-(U9A-1IN-)") (class "Default")
      (node (ref "C24") (pin "2") (pinfunction "2_2") (pintype "passive"))
      (node (ref "J10") (pin "2") (pinfunction "2_2") (pintype "passive"))
      (node (ref "U9") (pin "2") (pinfunction "1IN-_2") (pintype "input"))
    )
    (net (code "37") (name "Net-(U9A-1OUT)") (class "Default")
      (node (ref "J10") (pin "1") (pinfunction "1_1") (pintype "passive"))
      (node (ref "J8") (pin "2") (pinfunction "2_2") (pintype "passive"))
      (node (ref "U9") (pin "1") (pinfunction "1OUT_1") (pintype "output"))
    )
    (net (code "38") (name "Net-(U10A-1IN-)") (class "Default")
      (node (ref "J6") (pin "1") (pinfunction "1_1") (pintype "passive"))
      (node (ref "J7") (pin "1") (pinfunction "1_1") (pintype "passive"))
      (node (ref "J8") (pin "1") (pinfunction "1_1") (pintype "passive"))
      (node (ref "R35") (pin "2") (pinfunction "2_2") (pintype "passive"))
      (node (ref "U10") (pin "2") (pinfunction "1IN-_2") (pintype "input"))
    )
    (net (code "39") (name "Net-(U11-IN+)") (class "Default")
      (node (ref "J4") (pin "1") (pinfunction "1_1") (pintype "passive"))
      (node (ref "R31") (pin "2") (pinfunction "2_2") (pintype "passive"))
      (node (ref "U11") (pin "3") (pinfunction "IN+_3") (pintype "input"))
    )
    (net (code "40") (name "Net-(U11-IN-)") (class "Default")
      (node (ref "R38") (pin "1") (pinfunction "1_1") (pintype "passive"))
      (node (ref "U11") (pin "2") (pinfunction "IN-_2") (pintype "input"))
      (node (ref "U11") (pin "6") (pinfunction "OUT_6") (pintype "output"))
    )
    (net (code "41") (name "Net-(U13-IN+)") (class "Default")
      (node (ref "R30") (pin "2") (pinfunction "2_2") (pintype "passive"))
      (node (ref "R34") (pin "2") (pinfunction "2_2") (pintype "passive"))
      (node (ref "U13") (pin "3") (pinfunction "IN+_3") (pintype "input"))
    )
    (net (code "42") (name "Net-(U13-IN-)") (class "Default")
      (node (ref "R33") (pin "1") (pinfunction "1_1") (pintype "passive"))
      (node (ref "R99") (pin "2") (pinfunction "2_2") (pintype "passive"))
      (node (ref "U13") (pin "2") (pinfunction "IN-_2") (pintype "input"))
    )
    (net (code "43") (name "Net-(U13-OUT)") (class "Default")
      (node (ref "C23") (pin "1") (pinfunction "1_1") (pintype "passive"))
      (node (ref "R33") (pin "2") (pinfunction "2_2") (pintype "passive"))
      (node (ref "R34") (pin "1") (pinfunction "1_1") (pintype "passive"))
      (node (ref "U13") (pin "6") (pinfunction "OUT_6") (pintype "output"))
    )
    (net (code "44") (name "Net-(U14-IN+)") (class "Default")
      (node (ref "J3") (pin "2") (pinfunction "2_2") (pintype "passive"))
      (node (ref "R32") (pin "2") (pinfunction "2_2") (pintype "passive"))
      (node (ref "U14") (pin "3") (pinfunction "IN+_3") (pintype "input"))
    )
    (net (code "45") (name "Net-(U14-IN-)") (class "Default")
      (node (ref "R37") (pin "1") (pinfunction "1_1") (pintype "passive"))
      (node (ref "U14") (pin "2") (pinfunction "IN-_2") (pintype "input"))
      (node (ref "U14") (pin "6") (pinfunction "OUT_6") (pintype "output"))
    )
    (net (code "46") (name "Net-(U19-IN+)") (class "Default")
      (node (ref "R41") (pin "1") (pinfunction "1_1") (pintype "passive"))
      (node (ref "U19") (pin "3") (pinfunction "IN+_3") (pintype "input"))
    )
    (net (code "47") (name "Net-(U19-IN-)") (class "Default")
      (node (ref "C26") (pin "1") (pinfunction "1_1") (pintype "passive"))
      (node (ref "R39") (pin "1") (pinfunction "1_1") (pintype "passive"))
      (node (ref "R43") (pin "1") (pinfunction "1_1") (pintype "passive"))
      (node (ref "U19") (pin "2") (pinfunction "IN-_2") (pintype "input"))
    )
    (net (code "48") (name "Net-(U19-OUT)") (class "Default")
      (node (ref "C26") (pin "2") (pinfunction "2_2") (pintype "passive"))
      (node (ref "C62") (pin "1") (pinfunction "1_1") (pintype "passive"))
      (node (ref "R43") (pin "2") (pinfunction "2_2") (pintype "passive"))
      (node (ref "U19") (pin "6") (pinfunction "OUT_6") (pintype "output"))
    )
    (net (code "49") (name "Net-(U20-IN+)") (class "Default")
      (node (ref "R38") (pin "2") (pinfunction "2_2") (pintype "passive"))
      (node (ref "R42") (pin "2") (pinfunction "2_2") (pintype "passive"))
      (node (ref "U20") (pin "3") (pinfunction "IN+_3") (pintype "input"))
    )
    (net (code "50") (name "Net-(U20-IN-)") (class "Default")
      (node (ref "R37") (pin "2") (pinfunction "2_2") (pintype "passive"))
      (node (ref "R44") (pin "1") (pinfunction "1_1") (pintype "passive"))
      (node (ref "U20") (pin "2") (pinfunction "IN-_2") (pintype "input"))
    )
    (net (code "51") (name "Net-(U20-OUT)") (class "Default")
      (node (ref "R44") (pin "2") (pinfunction "2_2") (pintype "passive"))
      (node (ref "R50") (pin "1") (pinfunction "1_1") (pintype "passive"))
      (node (ref "U20") (pin "6") (pinfunction "OUT_6") (pintype "output"))
    )
    (net (code "52") (name "Net-(U21-IN-)") (class "Default")
      (node (ref "J12") (pin "2") (pinfunction "2_2") (pintype "passive"))
      (node (ref "R49") (pin "1") (pinfunction "1_1") (pintype "passive"))
      (node (ref "U21") (pin "2") (pinfunction "IN-_2") (pintype "input"))
    )
    (net (code "53") (name "Net-(U22-IN-)") (class "Default")
      (node (ref "J5") (pin "2") (pinfunction "2_2") (pintype "passive"))
      (node (ref "R50") (pin "2") (pinfunction "2_2") (pintype "passive"))
      (node (ref "U22") (pin "2") (pinfunction "IN-_2") (pintype "input"))
    )
    (net (code "54") (name "Net-(U32-OUT)") (class "Default")
      (node (ref "R78") (pin "1") (pinfunction "1_1") (pintype "passive"))
      (node (ref "U32") (pin "6") (pinfunction "OUT_6") (pintype "output"))
    )
    (net (code "55") (name "Net-(U33-OUT)") (class "Default")
      (node (ref "R53") (pin "1") (pinfunction "1_1") (pintype "passive"))
      (node (ref "U33") (pin "6") (pinfunction "OUT_6") (pintype "output"))
    )
    (net (code "56") (name "Net-(U34-OUT)") (class "Default")
      (node (ref "R54") (pin "1") (pinfunction "1_1") (pintype "passive"))
      (node (ref "U34") (pin "6") (pinfunction "OUT_6") (pintype "output"))
    )
    (net (code "57") (name "Net-(power_supply+-port)") (class "Default")
      (node (ref "SW1") (pin "2") (pinfunction "2_2") (pintype "passive"))
      (node (ref "power_supply+") (pin "1") (pinfunction "port_1") (pintype "passive"))
    )
    (net (code "58") (name "Net-(power_supply--port)") (class "Default")
      (node (ref "SW2") (pin "2") (pinfunction "2_2") (pintype "passive"))
      (node (ref "power_supply-") (pin "1") (pinfunction "port_1") (pintype "passive"))
    )
    (net (code "59") (name "unconnected-(R31-Pad3)") (class "Default")
      (node (ref "R31") (pin "3") (pinfunction "3_3") (pintype "passive+no_connect"))
    )
    (net (code "60") (name "unconnected-(R32-Pad3)") (class "Default")
      (node (ref "R32") (pin "3") (pinfunction "3_3") (pintype "passive+no_connect"))
    )
    (net (code "61") (name "unconnected-(U11-NC-Pad8)") (class "Default")
      (node (ref "U11") (pin "8") (pinfunction "NC_8") (pintype "passive+no_connect"))
    )
    (net (code "62") (name "unconnected-(U11-OFFSET_N1-Pad1)") (class "Default")
      (node (ref "U11") (pin "1") (pinfunction "OFFSET_N1_1") (pintype "input+no_connect"))
    )
    (net (code "63") (name "unconnected-(U11-OFFSET_N2-Pad5)") (class "Default")
      (node (ref "U11") (pin "5") (pinfunction "OFFSET_N2_5") (pintype "input+no_connect"))
    )
    (net (code "64") (name "unconnected-(U13-NC-Pad8)") (class "Default")
      (node (ref "U13") (pin "8") (pinfunction "NC_8") (pintype "passive+no_connect"))
    )
    (net (code "65") (name "unconnected-(U13-OFFSET_N1-Pad1)") (class "Default")
      (node (ref "U13") (pin "1") (pinfunction "OFFSET_N1_1") (pintype "input+no_connect"))
    )
    (net (code "66") (name "unconnected-(U13-OFFSET_N2-Pad5)") (class "Default")
      (node (ref "U13") (pin "5") (pinfunction "OFFSET_N2_5") (pintype "input+no_connect"))
    )
    (net (code "67") (name "unconnected-(U14-NC-Pad8)") (class "Default")
      (node (ref "U14") (pin "8") (pinfunction "NC_8") (pintype "passive+no_connect"))
    )
    (net (code "68") (name "unconnected-(U14-OFFSET_N1-Pad1)") (class "Default")
      (node (ref "U14") (pin "1") (pinfunction "OFFSET_N1_1") (pintype "input+no_connect"))
    )
    (net (code "69") (name "unconnected-(U14-OFFSET_N2-Pad5)") (class "Default")
      (node (ref "U14") (pin "5") (pinfunction "OFFSET_N2_5") (pintype "input+no_connect"))
    )
    (net (code "70") (name "unconnected-(U19-NC-Pad8)") (class "Default")
      (node (ref "U19") (pin "8") (pinfunction "NC_8") (pintype "passive+no_connect"))
    )
    (net (code "71") (name "unconnected-(U19-OFFSET_N1-Pad1)") (class "Default")
      (node (ref "U19") (pin "1") (pinfunction "OFFSET_N1_1") (pintype "input+no_connect"))
    )
    (net (code "72") (name "unconnected-(U19-OFFSET_N2-Pad5)") (class "Default")
      (node (ref "U19") (pin "5") (pinfunction "OFFSET_N2_5") (pintype "input+no_connect"))
    )
    (net (code "73") (name "unconnected-(U20-NC-Pad8)") (class "Default")
      (node (ref "U20") (pin "8") (pinfunction "NC_8") (pintype "passive+no_connect"))
    )
    (net (code "74") (name "unconnected-(U20-OFFSET_N1-Pad1)") (class "Default")
      (node (ref "U20") (pin "1") (pinfunction "OFFSET_N1_1") (pintype "input+no_connect"))
    )
    (net (code "75") (name "unconnected-(U20-OFFSET_N2-Pad5)") (class "Default")
      (node (ref "U20") (pin "5") (pinfunction "OFFSET_N2_5") (pintype "input+no_connect"))
    )
    (net (code "76") (name "unconnected-(U21-NC-Pad8)") (class "Default")
      (node (ref "U21") (pin "8") (pinfunction "NC_8") (pintype "passive+no_connect"))
    )
    (net (code "77") (name "unconnected-(U21-OFFSET_N1-Pad1)") (class "Default")
      (node (ref "U21") (pin "1") (pinfunction "OFFSET_N1_1") (pintype "input+no_connect"))
    )
    (net (code "78") (name "unconnected-(U21-OFFSET_N2-Pad5)") (class "Default")
      (node (ref "U21") (pin "5") (pinfunction "OFFSET_N2_5") (pintype "input+no_connect"))
    )
    (net (code "79") (name "unconnected-(U22-NC-Pad8)") (class "Default")
      (node (ref "U22") (pin "8") (pinfunction "NC_8") (pintype "passive+no_connect"))
    )
    (net (code "80") (name "unconnected-(U22-OFFSET_N1-Pad1)") (class "Default")
      (node (ref "U22") (pin "1") (pinfunction "OFFSET_N1_1") (pintype "input+no_connect"))
    )
    (net (code "81") (name "unconnected-(U22-OFFSET_N2-Pad5)") (class "Default")
      (node (ref "U22") (pin "5") (pinfunction "OFFSET_N2_5") (pintype "input+no_connect"))
    )
    (net (code "82") (name "unconnected-(U32-BAL{slash}COMP1-Pad1)") (class "Default")
      (node (ref "U32") (pin "1") (pinfunction "BAL/COMP1_1") (pintype "passive+no_connect"))
    )
    (net (code "83") (name "unconnected-(U32-BAL{slash}COMP3-Pad5)") (class "Default")
      (node (ref "U32") (pin "5") (pinfunction "BAL/COMP3_5") (pintype "passive+no_connect"))
    )
    (net (code "84") (name "unconnected-(U32-COMP2-Pad8)") (class "Default")
      (node (ref "U32") (pin "8") (pinfunction "COMP2_8") (pintype "passive+no_connect"))
    )
    (net (code "85") (name "unconnected-(U33-BAL{slash}COMP1-Pad1)") (class "Default")
      (node (ref "U33") (pin "1") (pinfunction "BAL/COMP1_1") (pintype "passive+no_connect"))
    )
    (net (code "86") (name "unconnected-(U33-BAL{slash}COMP3-Pad5)") (class "Default")
      (node (ref "U33") (pin "5") (pinfunction "BAL/COMP3_5") (pintype "passive+no_connect"))
    )
    (net (code "87") (name "unconnected-(U33-COMP2-Pad8)") (class "Default")
      (node (ref "U33") (pin "8") (pinfunction "COMP2_8") (pintype "passive+no_connect"))
    )
    (net (code "88") (name "unconnected-(U34-BAL{slash}COMP1-Pad1)") (class "Default")
      (node (ref "U34") (pin "1") (pinfunction "BAL/COMP1_1") (pintype "passive+no_connect"))
    )
    (net (code "89") (name "unconnected-(U34-BAL{slash}COMP3-Pad5)") (class "Default")
      (node (ref "U34") (pin "5") (pinfunction "BAL/COMP3_5") (pintype "passive+no_connect"))
    )
    (net (code "90") (name "unconnected-(U34-COMP2-Pad8)") (class "Default")
      (node (ref "U34") (pin "8") (pinfunction "COMP2_8") (pintype "passive+no_connect"))
    )
    (net (code "91") (name "unconnected-(VR1-CW-Pad3)") (class "Default")
      (node (ref "VR1") (pin "3") (pinfunction "CW_3") (pintype "passive+no_connect"))
    )
  )
)
